# M840X.net
KiCad netlist of a schematic drawn in EAGLE
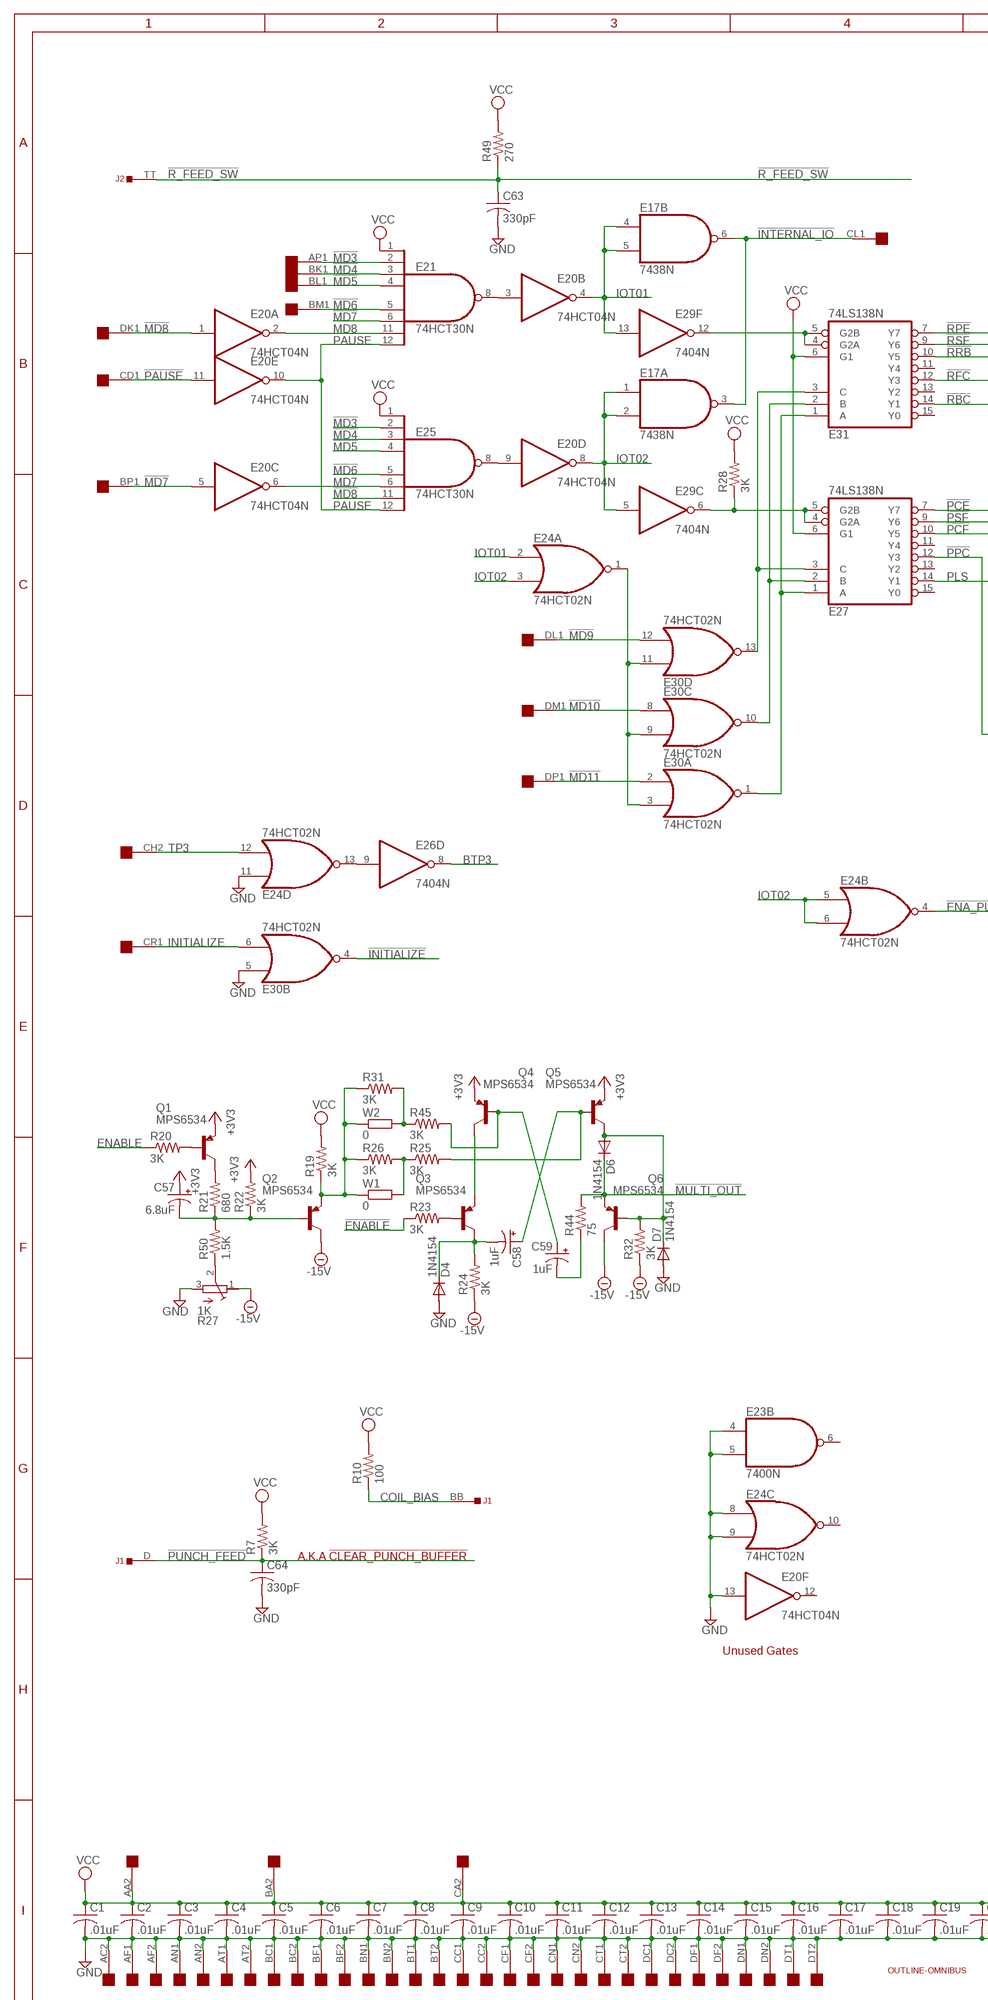
[diagram p0: schematic, sheet 1, part 1 of 2]
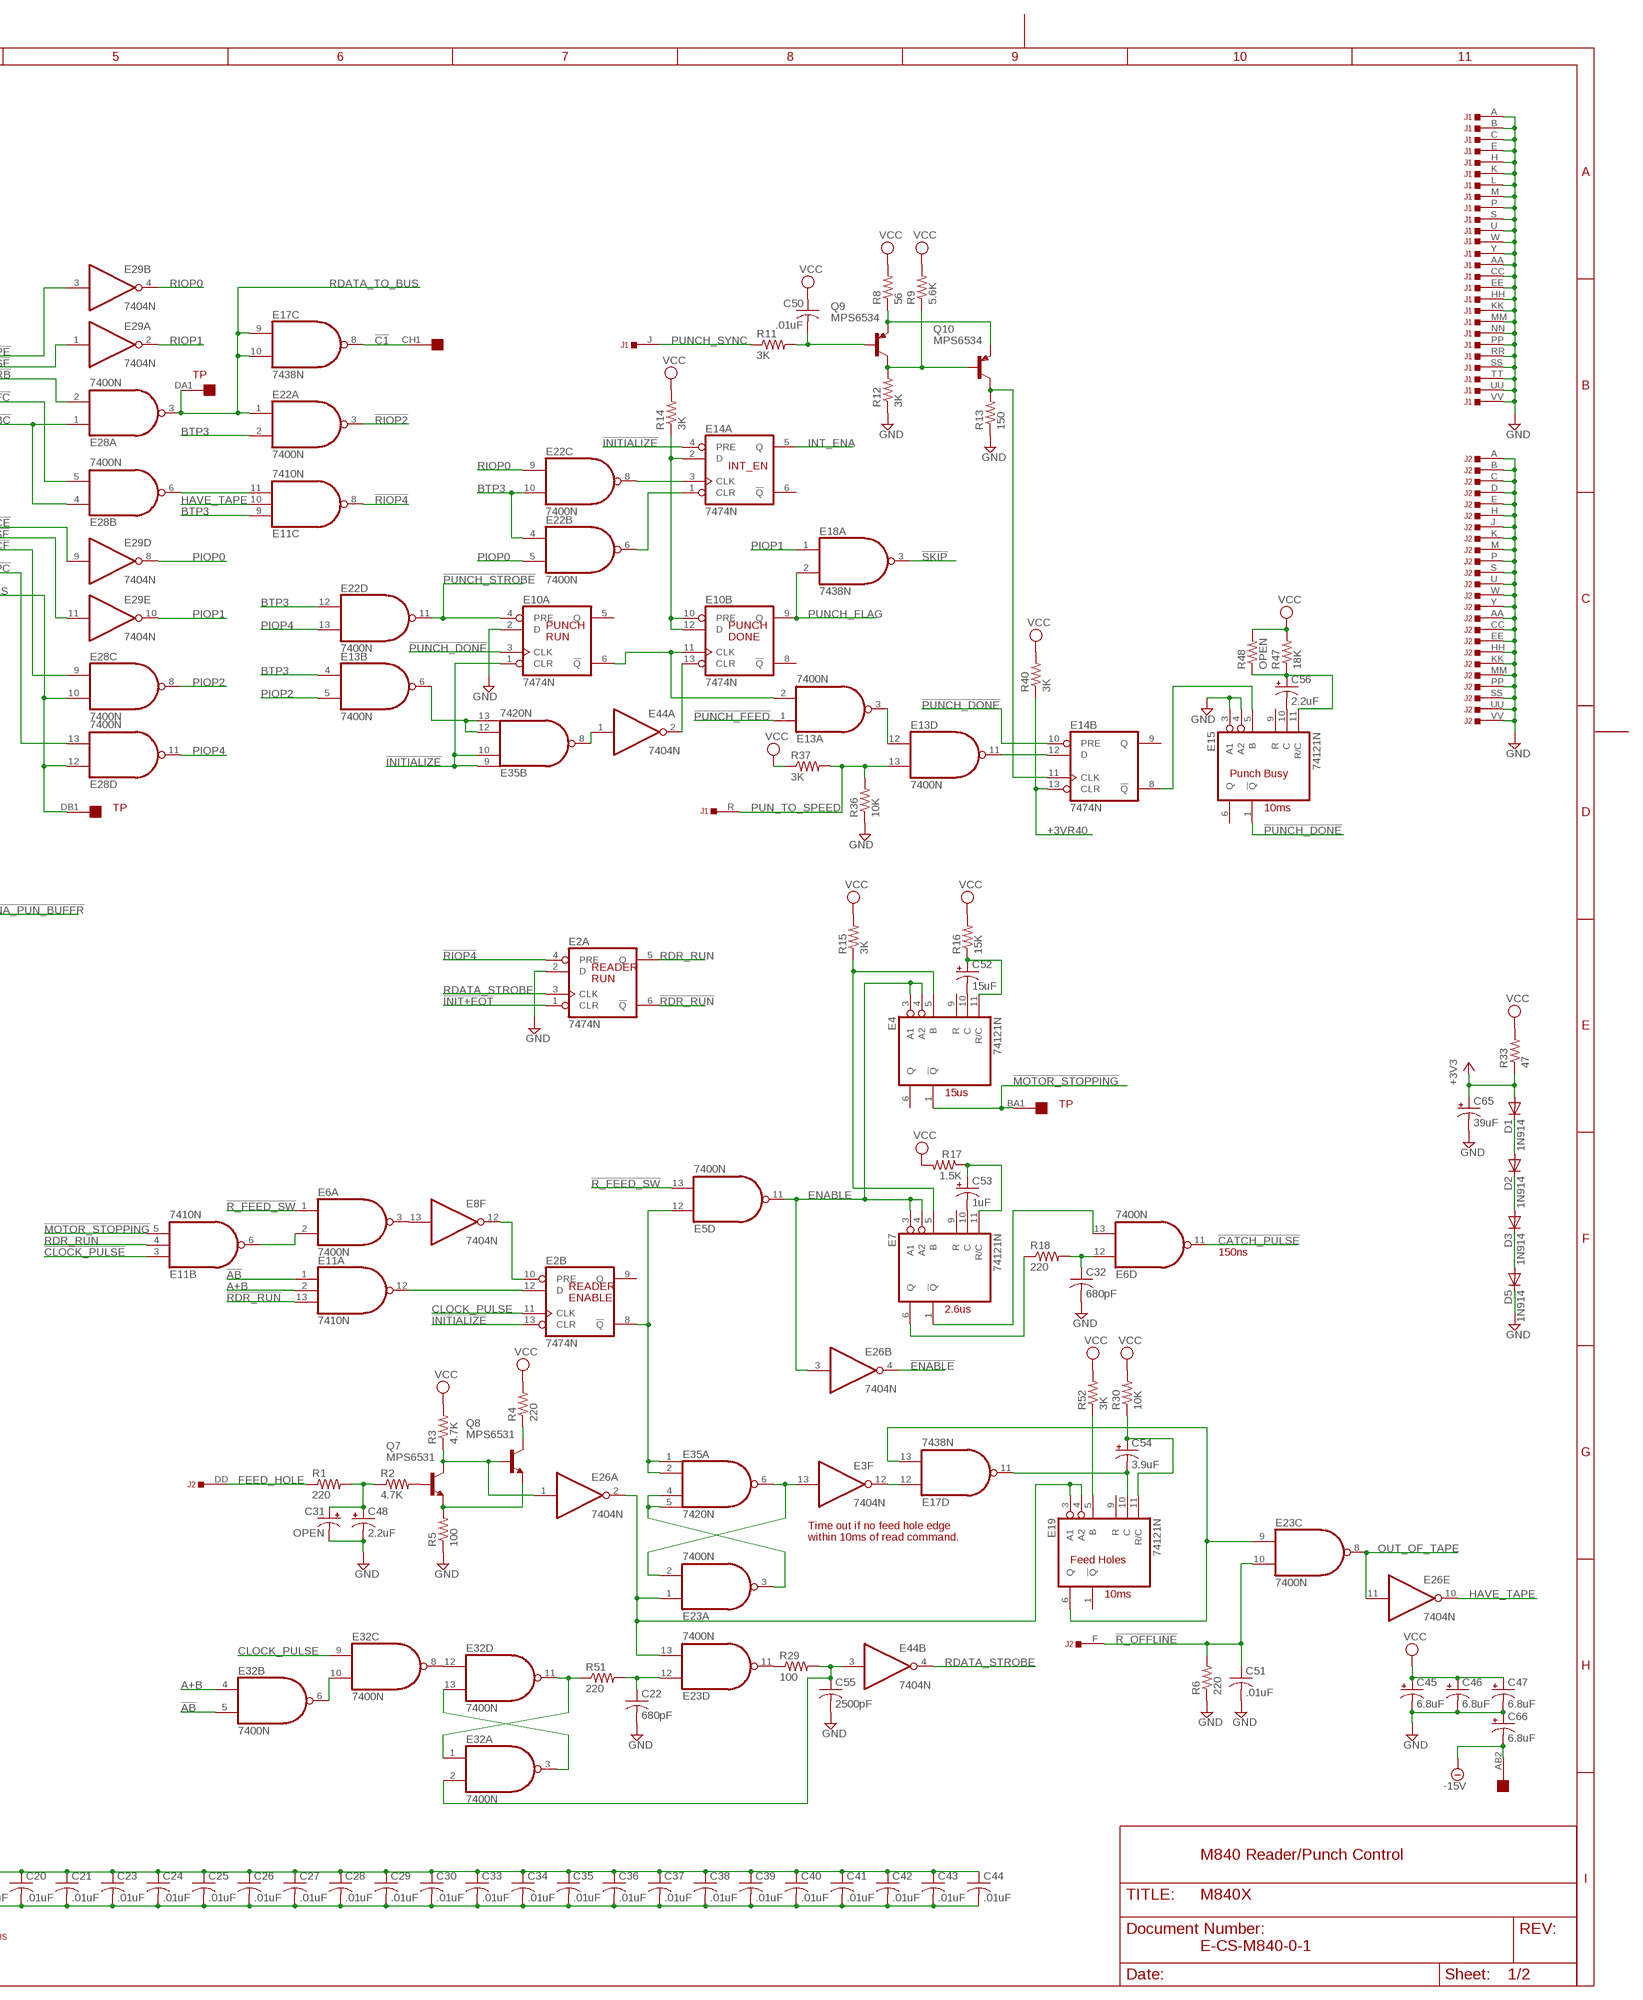
[diagram p1: schematic, sheet 1, part 2 of 2]
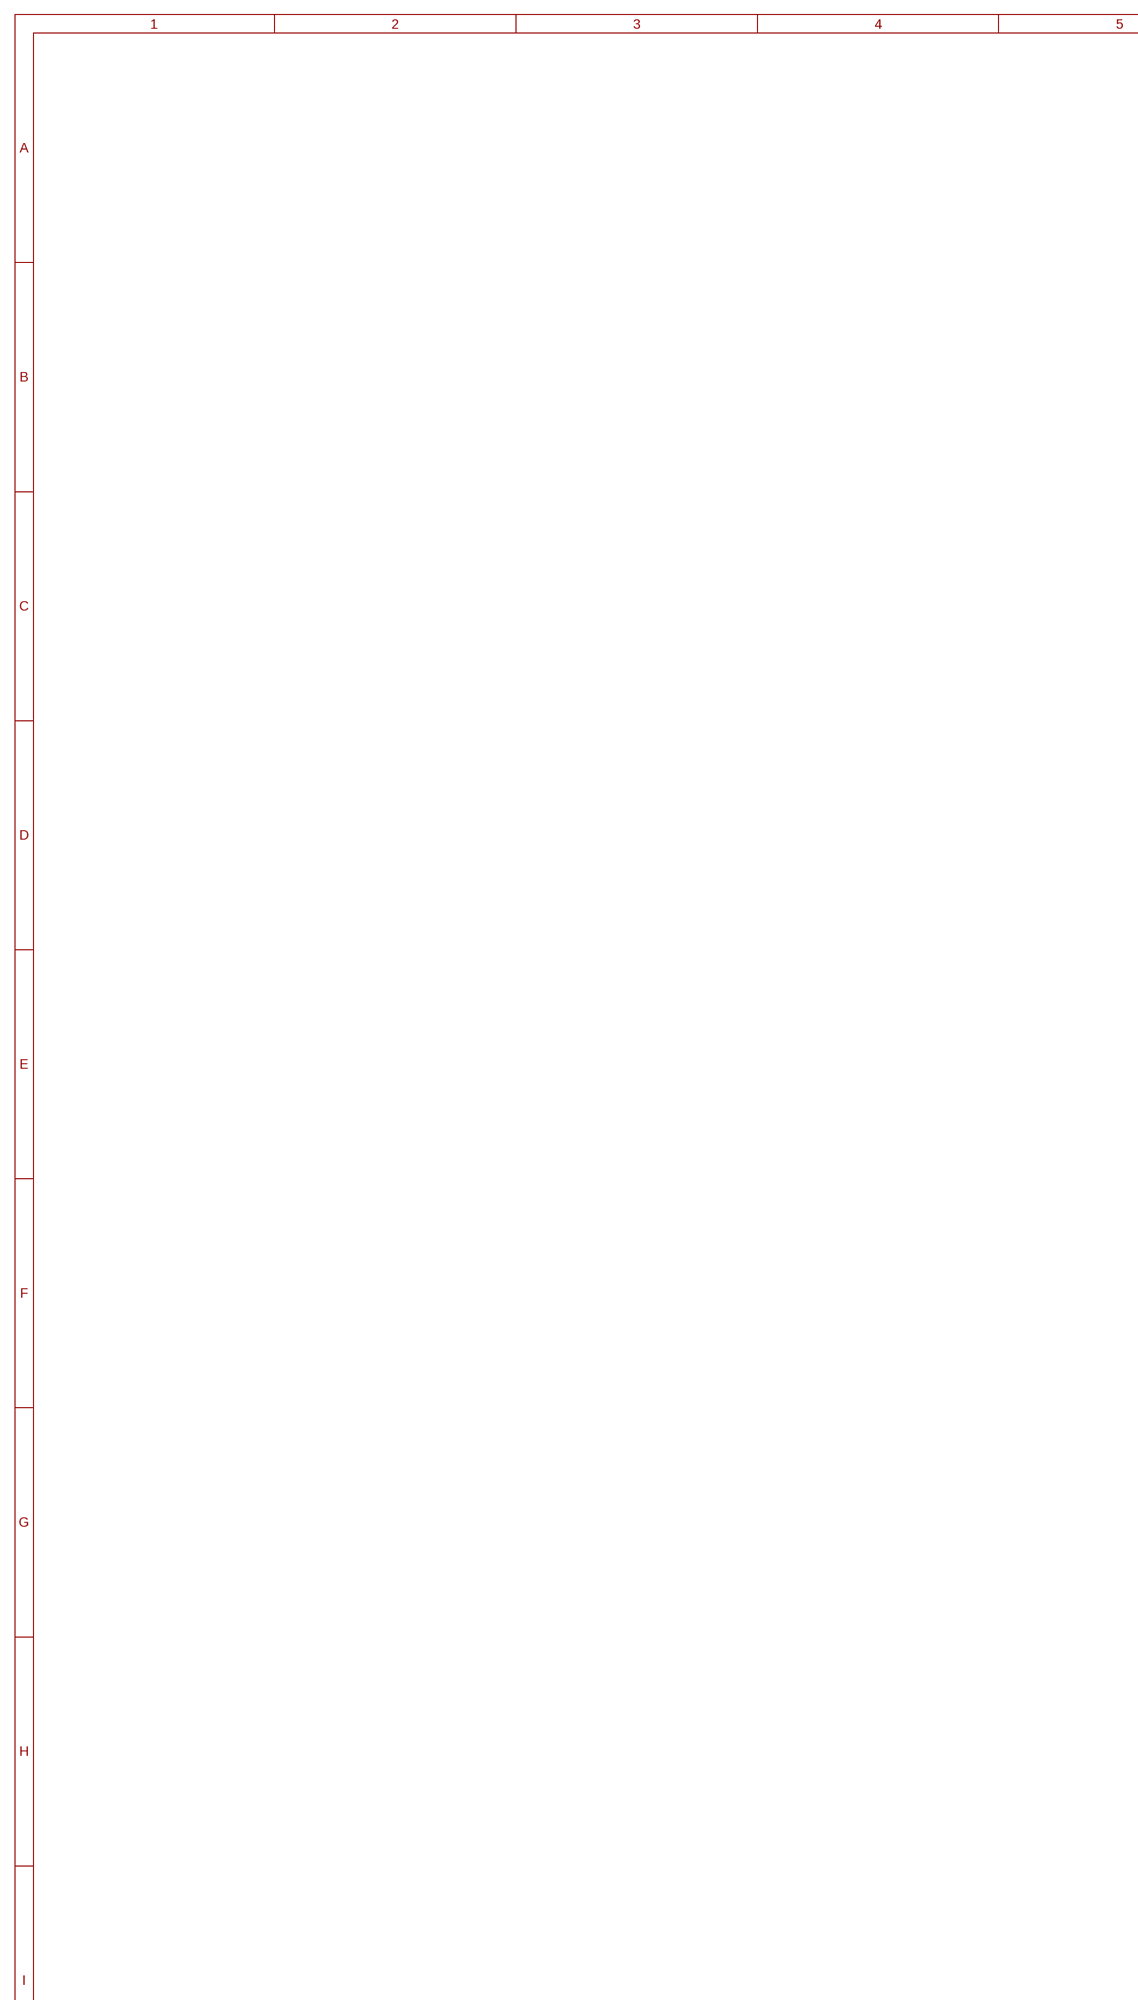
[diagram p2: schematic, sheet 2, part 1 of 2]
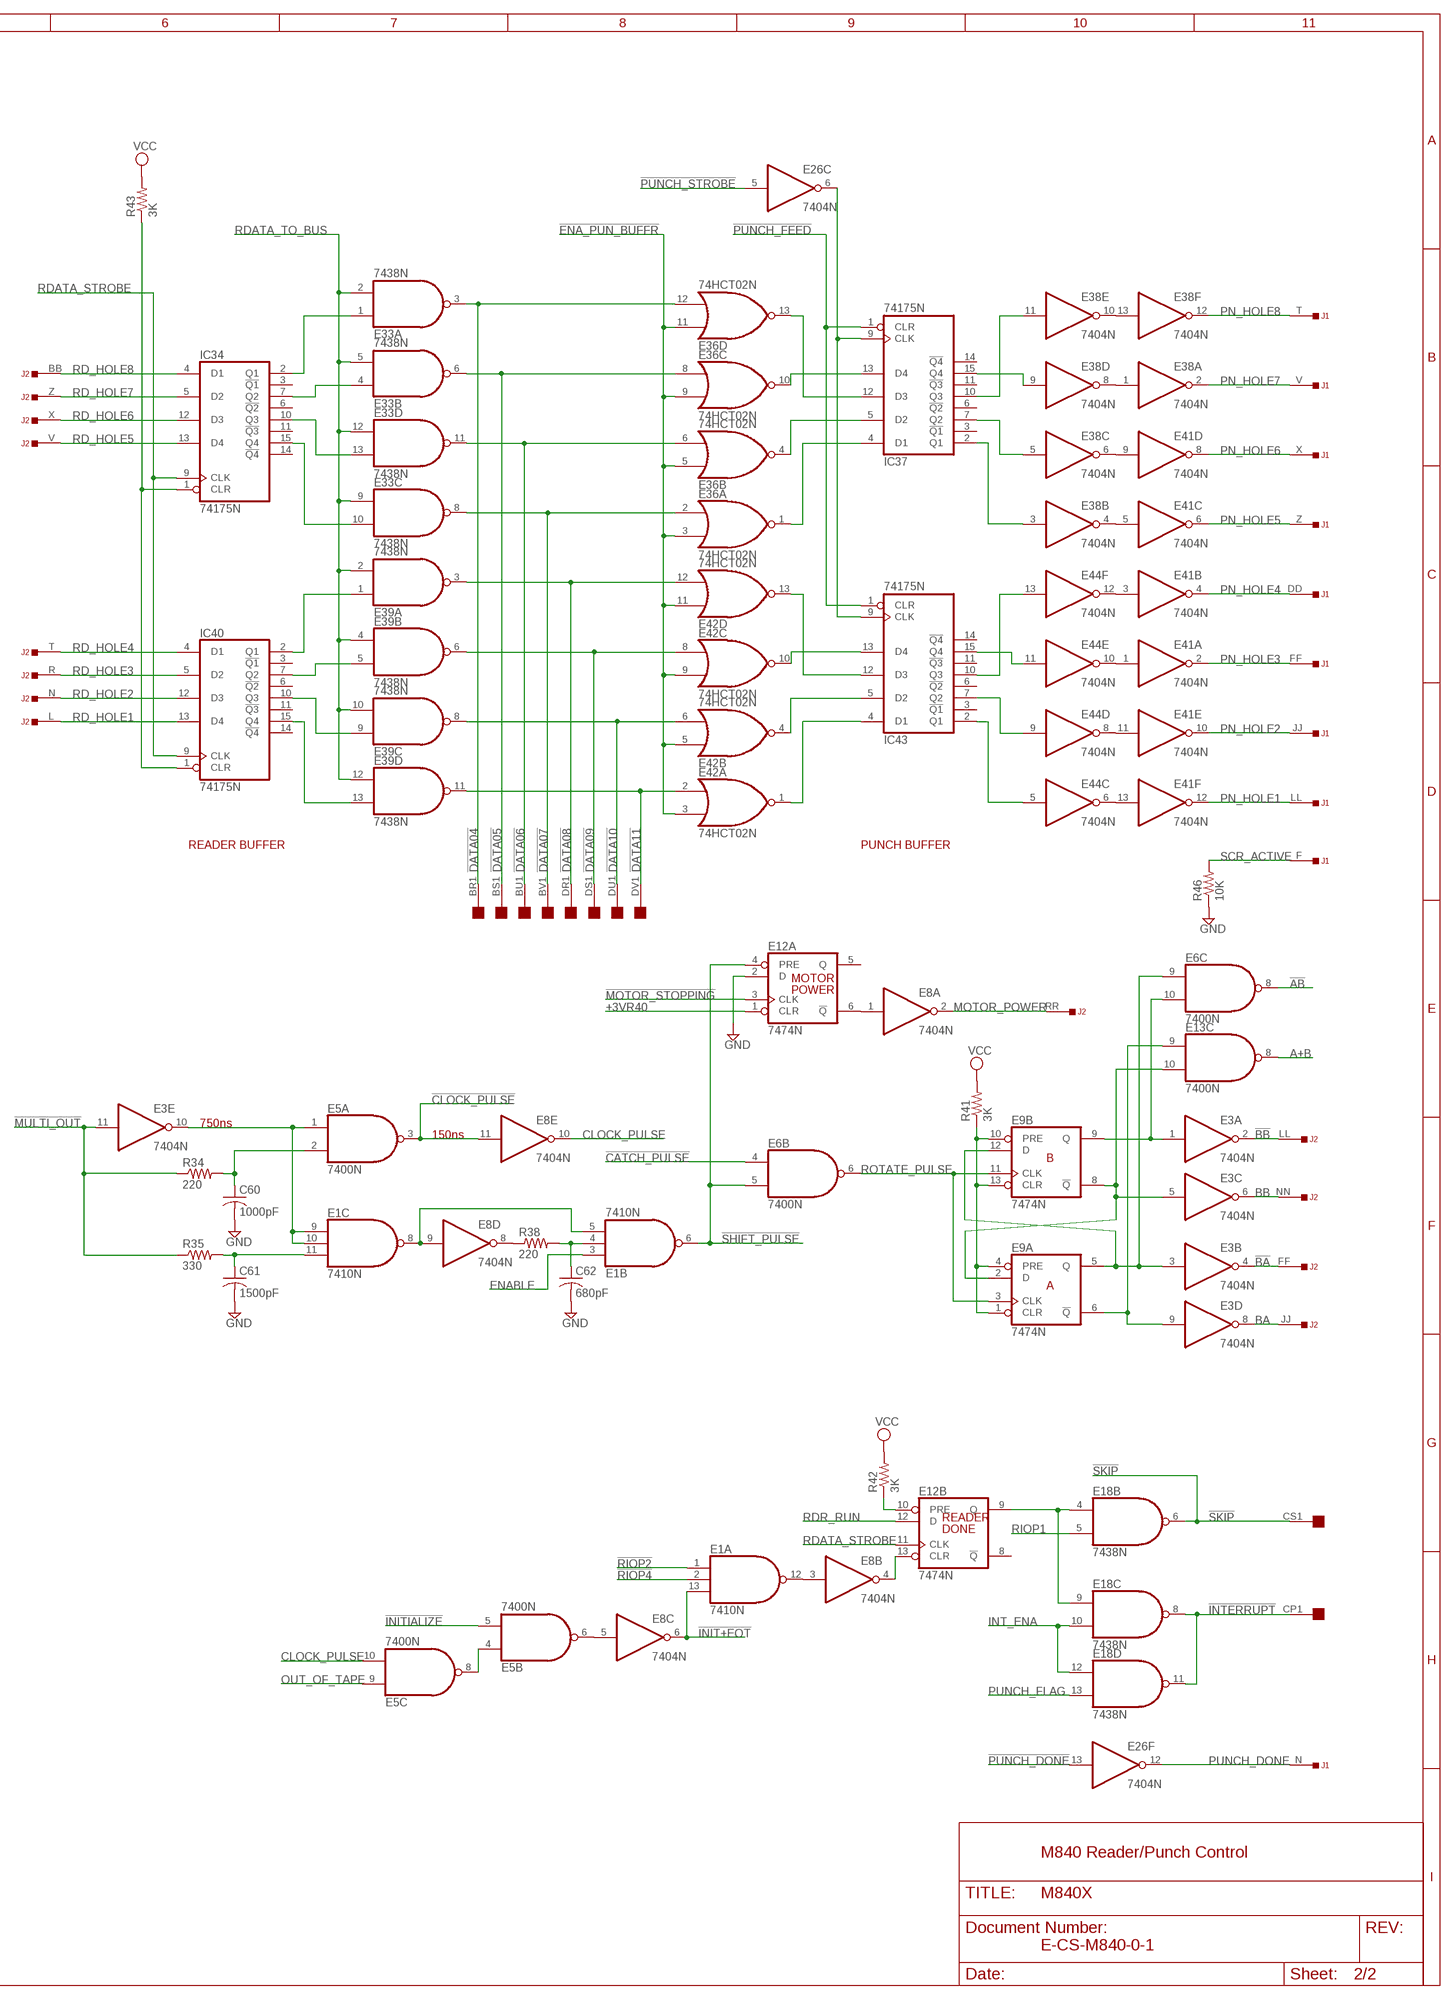
[diagram p3: schematic, sheet 2, part 2 of 2]

(export (version "E")
  (design (tool "Eeschema 10.0.6"))
  (components
    (comp (ref "C1")
      (value ".01uF")
      (footprint "eagle-import:C063-025X075")
      (libsource (lib "eagle-import") (part "C-US"))
    )
    (comp (ref "C2")
      (value ".01uF")
      (footprint "eagle-import:C063-025X075")
      (libsource (lib "eagle-import") (part "C-US"))
    )
    (comp (ref "C3")
      (value ".01uF")
      (footprint "eagle-import:C063-025X075")
      (libsource (lib "eagle-import") (part "C-US"))
    )
    (comp (ref "C4")
      (value ".01uF")
      (footprint "eagle-import:C063-025X075")
      (libsource (lib "eagle-import") (part "C-US"))
    )
    (comp (ref "C5")
      (value ".01uF")
      (footprint "eagle-import:C063-025X075")
      (libsource (lib "eagle-import") (part "C-US"))
    )
    (comp (ref "C6")
      (value ".01uF")
      (footprint "eagle-import:C063-025X075")
      (libsource (lib "eagle-import") (part "C-US"))
    )
    (comp (ref "C7")
      (value ".01uF")
      (footprint "eagle-import:C063-025X075")
      (libsource (lib "eagle-import") (part "C-US"))
    )
    (comp (ref "C8")
      (value ".01uF")
      (footprint "eagle-import:C063-025X075")
      (libsource (lib "eagle-import") (part "C-US"))
    )
    (comp (ref "C9")
      (value ".01uF")
      (footprint "eagle-import:C063-025X075")
      (libsource (lib "eagle-import") (part "C-US"))
    )
    (comp (ref "C10")
      (value ".01uF")
      (footprint "eagle-import:C063-025X075")
      (libsource (lib "eagle-import") (part "C-US"))
    )
    (comp (ref "C11")
      (value ".01uF")
      (footprint "eagle-import:C063-025X075")
      (libsource (lib "eagle-import") (part "C-US"))
    )
    (comp (ref "C12")
      (value ".01uF")
      (footprint "eagle-import:C063-025X075")
      (libsource (lib "eagle-import") (part "C-US"))
    )
    (comp (ref "C13")
      (value ".01uF")
      (footprint "eagle-import:C063-025X075")
      (libsource (lib "eagle-import") (part "C-US"))
    )
    (comp (ref "C14")
      (value ".01uF")
      (footprint "eagle-import:C063-025X075")
      (libsource (lib "eagle-import") (part "C-US"))
    )
    (comp (ref "C15")
      (value ".01uF")
      (footprint "eagle-import:C063-025X075")
      (libsource (lib "eagle-import") (part "C-US"))
    )
    (comp (ref "C16")
      (value ".01uF")
      (footprint "eagle-import:C063-025X075")
      (libsource (lib "eagle-import") (part "C-US"))
    )
    (comp (ref "C17")
      (value ".01uF")
      (footprint "eagle-import:C063-025X075")
      (libsource (lib "eagle-import") (part "C-US"))
    )
    (comp (ref "C18")
      (value ".01uF")
      (footprint "eagle-import:C063-025X075")
      (libsource (lib "eagle-import") (part "C-US"))
    )
    (comp (ref "C19")
      (value ".01uF")
      (footprint "eagle-import:C063-025X075")
      (libsource (lib "eagle-import") (part "C-US"))
    )
    (comp (ref "C20")
      (value ".01uF")
      (footprint "eagle-import:C063-025X075")
      (libsource (lib "eagle-import") (part "C-US"))
    )
    (comp (ref "C21")
      (value ".01uF")
      (footprint "eagle-import:C063-025X075")
      (libsource (lib "eagle-import") (part "C-US"))
    )
    (comp (ref "C22")
      (value "680pF")
      (footprint "eagle-import:C063-025X075")
      (libsource (lib "eagle-import") (part "C-US"))
    )
    (comp (ref "C23")
      (value ".01uF")
      (footprint "eagle-import:C063-025X075")
      (libsource (lib "eagle-import") (part "C-US"))
    )
    (comp (ref "C24")
      (value ".01uF")
      (footprint "eagle-import:C063-025X075")
      (libsource (lib "eagle-import") (part "C-US"))
    )
    (comp (ref "C25")
      (value ".01uF")
      (footprint "eagle-import:C063-025X075")
      (libsource (lib "eagle-import") (part "C-US"))
    )
    (comp (ref "C26")
      (value ".01uF")
      (footprint "eagle-import:C063-025X075")
      (libsource (lib "eagle-import") (part "C-US"))
    )
    (comp (ref "C27")
      (value ".01uF")
      (footprint "eagle-import:C063-025X075")
      (libsource (lib "eagle-import") (part "C-US"))
    )
    (comp (ref "C28")
      (value ".01uF")
      (footprint "eagle-import:C063-025X075")
      (libsource (lib "eagle-import") (part "C-US"))
    )
    (comp (ref "C29")
      (value ".01uF")
      (footprint "eagle-import:C063-025X075")
      (libsource (lib "eagle-import") (part "C-US"))
    )
    (comp (ref "C30")
      (value ".01uF")
      (footprint "eagle-import:C063-025X075")
      (libsource (lib "eagle-import") (part "C-US"))
    )
    (comp (ref "C31")
      (value "OPEN")
      (footprint "eagle-import:E15-5")
      (libsource (lib "eagle-import") (part "CPOL-USE15-5AXIAL"))
    )
    (comp (ref "C32")
      (value "680pF")
      (footprint "eagle-import:C063-025X075")
      (libsource (lib "eagle-import") (part "C-US"))
    )
    (comp (ref "C33")
      (value ".01uF")
      (footprint "eagle-import:C063-025X075")
      (libsource (lib "eagle-import") (part "C-US"))
    )
    (comp (ref "C34")
      (value ".01uF")
      (footprint "eagle-import:C063-025X075")
      (libsource (lib "eagle-import") (part "C-US"))
    )
    (comp (ref "C35")
      (value ".01uF")
      (footprint "eagle-import:C063-025X075")
      (libsource (lib "eagle-import") (part "C-US"))
    )
    (comp (ref "C36")
      (value ".01uF")
      (footprint "eagle-import:C063-025X075")
      (libsource (lib "eagle-import") (part "C-US"))
    )
    (comp (ref "C37")
      (value ".01uF")
      (footprint "eagle-import:C063-025X075")
      (libsource (lib "eagle-import") (part "C-US"))
    )
    (comp (ref "C38")
      (value ".01uF")
      (footprint "eagle-import:C063-025X075")
      (libsource (lib "eagle-import") (part "C-US"))
    )
    (comp (ref "C39")
      (value ".01uF")
      (footprint "eagle-import:C063-025X075")
      (libsource (lib "eagle-import") (part "C-US"))
    )
    (comp (ref "C40")
      (value ".01uF")
      (footprint "eagle-import:C063-025X075")
      (libsource (lib "eagle-import") (part "C-US"))
    )
    (comp (ref "C41")
      (value ".01uF")
      (footprint "eagle-import:C063-025X075")
      (libsource (lib "eagle-import") (part "C-US"))
    )
    (comp (ref "C42")
      (value ".01uF")
      (footprint "eagle-import:C063-025X075")
      (libsource (lib "eagle-import") (part "C-US"))
    )
    (comp (ref "C43")
      (value ".01uF")
      (footprint "eagle-import:C063-025X075")
      (libsource (lib "eagle-import") (part "C-US"))
    )
    (comp (ref "C44")
      (value ".01uF")
      (footprint "eagle-import:C063-025X075")
      (libsource (lib "eagle-import") (part "C-US"))
    )
    (comp (ref "C45")
      (value "6.8uF")
      (footprint "eagle-import:E12-8")
      (libsource (lib "eagle-import") (part "CPOL-USE20-8AXIAL"))
    )
    (comp (ref "C46")
      (value "6.8uF")
      (footprint "eagle-import:E12-8")
      (libsource (lib "eagle-import") (part "CPOL-USE20-8AXIAL"))
    )
    (comp (ref "C47")
      (value "6.8uF")
      (footprint "eagle-import:E12-8")
      (libsource (lib "eagle-import") (part "CPOL-USE20-8AXIAL"))
    )
    (comp (ref "C48")
      (value "2.2uF")
      (footprint "eagle-import:E15-5")
      (libsource (lib "eagle-import") (part "CPOL-USE15-5AXIAL"))
    )
    (comp (ref "C50")
      (value ".01uF")
      (footprint "eagle-import:C203-054-229")
      (libsource (lib "eagle-import") (part "C-US8"))
    )
    (comp (ref "C51")
      (value ".01uF")
      (footprint "eagle-import:C203-054-229")
      (libsource (lib "eagle-import") (part "C-US8"))
    )
    (comp (ref "C52")
      (value "15uF")
      (footprint "eagle-import:E12-8")
      (libsource (lib "eagle-import") (part "CPOL-USE20-8AXIAL"))
    )
    (comp (ref "C53")
      (value "1uF")
      (footprint "eagle-import:E15-5")
      (libsource (lib "eagle-import") (part "CPOL-USE15-5AXIAL"))
    )
    (comp (ref "C54")
      (value "3.9uF")
      (footprint "eagle-import:E15-5")
      (libsource (lib "eagle-import") (part "CPOL-USE15-5AXIAL"))
    )
    (comp (ref "C55")
      (value "2500pF")
      (footprint "eagle-import:C063-025X075")
      (libsource (lib "eagle-import") (part "C-US"))
    )
    (comp (ref "C56")
      (value "2.2uF")
      (footprint "eagle-import:E15-5")
      (libsource (lib "eagle-import") (part "CPOL-USE15-5AXIAL"))
    )
    (comp (ref "C57")
      (value "6.8uF")
      (footprint "eagle-import:E12-8")
      (libsource (lib "eagle-import") (part "CPOL-USE20-8AXIAL"))
    )
    (comp (ref "C58")
      (value "1uF")
      (footprint "eagle-import:E15-5")
      (libsource (lib "eagle-import") (part "CPOL-USE15-5AXIAL"))
    )
    (comp (ref "C59")
      (value "1uF")
      (footprint "eagle-import:E15-5")
      (libsource (lib "eagle-import") (part "CPOL-USE15-5AXIAL"))
    )
    (comp (ref "C63")
      (value "330pF")
      (footprint "eagle-import:C063-025X075")
      (libsource (lib "eagle-import") (part "C-US"))
    )
    (comp (ref "C64")
      (value "330pF")
      (footprint "eagle-import:C063-025X075")
      (libsource (lib "eagle-import") (part "C-US"))
    )
    (comp (ref "C65")
      (value "39uF")
      (footprint "eagle-import:E12-8")
      (libsource (lib "eagle-import") (part "CPOL-USE20-8AXIAL"))
    )
    (comp (ref "C66")
      (value "6.8uF")
      (footprint "eagle-import:E12-8")
      (libsource (lib "eagle-import") (part "CPOL-USE20-8AXIAL"))
    )
    (comp (ref "D1")
      (value "1N914")
      (footprint "eagle-import:DO35-10")
      (libsource (lib "eagle-import") (part "DIODE-DO35-10"))
    )
    (comp (ref "D2")
      (value "1N914")
      (footprint "eagle-import:DO35-10")
      (libsource (lib "eagle-import") (part "DIODE-DO35-10"))
    )
    (comp (ref "D3")
      (value "1N914")
      (footprint "eagle-import:DO35-10")
      (libsource (lib "eagle-import") (part "DIODE-DO35-10"))
    )
    (comp (ref "D4")
      (value "1N4154")
      (footprint "eagle-import:DO35-10")
      (libsource (lib "eagle-import") (part "DIODE-DO35-10"))
    )
    (comp (ref "D5")
      (value "1N914")
      (footprint "eagle-import:DO35-10")
      (libsource (lib "eagle-import") (part "DIODE-DO35-10"))
    )
    (comp (ref "D6")
      (value "1N4154")
      (footprint "eagle-import:DO35-10")
      (libsource (lib "eagle-import") (part "DIODE-DO35-10"))
    )
    (comp (ref "D7")
      (value "1N4154")
      (footprint "eagle-import:DO35-10")
      (libsource (lib "eagle-import") (part "DIODE-DO35-10"))
    )
    (comp (ref "E2")
      (value "7474N")
      (footprint "eagle-import:DIL14")
      (libsource (lib "eagle-import") (part "7474NS"))
    )
    (comp (ref "E3")
      (value "7404N")
      (footprint "eagle-import:DIL14")
      (libsource (lib "eagle-import") (part "7404N"))
    )
    (comp (ref "E4")
      (value "74121N")
      (footprint "eagle-import:DIL14")
      (libsource (lib "eagle-import") (part "74121N"))
    )
    (comp (ref "E5")
      (value "7400N")
      (footprint "eagle-import:DIL14")
      (libsource (lib "eagle-import") (part "7400N"))
    )
    (comp (ref "E6")
      (value "7400N")
      (footprint "eagle-import:DIL14")
      (libsource (lib "eagle-import") (part "7400N"))
    )
    (comp (ref "E7")
      (value "74121N")
      (footprint "eagle-import:DIL14")
      (libsource (lib "eagle-import") (part "74121N"))
    )
    (comp (ref "E8")
      (value "7404N")
      (footprint "eagle-import:DIL14")
      (libsource (lib "eagle-import") (part "7404N"))
    )
    (comp (ref "E10")
      (value "7474N")
      (footprint "eagle-import:DIL14")
      (libsource (lib "eagle-import") (part "7474NS"))
    )
    (comp (ref "E11")
      (value "7410N")
      (footprint "eagle-import:DIL14")
      (libsource (lib "eagle-import") (part "7410N"))
    )
    (comp (ref "E13")
      (value "7400N")
      (footprint "eagle-import:DIL14")
      (libsource (lib "eagle-import") (part "7400N"))
    )
    (comp (ref "E14")
      (value "7474N")
      (footprint "eagle-import:DIL14")
      (libsource (lib "eagle-import") (part "7474NS"))
    )
    (comp (ref "E15")
      (value "74121N")
      (footprint "eagle-import:DIL14")
      (libsource (lib "eagle-import") (part "74121N"))
    )
    (comp (ref "E17")
      (value "7438N")
      (footprint "eagle-import:DIL14")
      (libsource (lib "eagle-import") (part "7438N"))
    )
    (comp (ref "E18")
      (value "7438N")
      (footprint "eagle-import:DIL14")
      (libsource (lib "eagle-import") (part "7438N"))
    )
    (comp (ref "E19")
      (value "74121N")
      (footprint "eagle-import:DIL14")
      (libsource (lib "eagle-import") (part "74121N"))
    )
    (comp (ref "E20")
      (value "74HCT04N")
      (footprint "eagle-import:DIL14")
      (libsource (lib "eagle-import") (part "7404N"))
    )
    (comp (ref "E21")
      (value "74HCT30N")
      (footprint "eagle-import:DIL14")
      (libsource (lib "eagle-import") (part "7430NLS"))
    )
    (comp (ref "E22")
      (value "7400N")
      (footprint "eagle-import:DIL14")
      (libsource (lib "eagle-import") (part "7400N"))
    )
    (comp (ref "E23")
      (value "7400N")
      (footprint "eagle-import:DIL14")
      (libsource (lib "eagle-import") (part "7400N"))
    )
    (comp (ref "E24")
      (value "74HCT02N")
      (footprint "eagle-import:DIL14")
      (libsource (lib "eagle-import") (part "7402NLS"))
    )
    (comp (ref "E25")
      (value "74HCT30N")
      (footprint "eagle-import:DIL14")
      (libsource (lib "eagle-import") (part "7430NLS"))
    )
    (comp (ref "E26")
      (value "7404N")
      (footprint "eagle-import:DIL14")
      (libsource (lib "eagle-import") (part "7404N"))
    )
    (comp (ref "E27")
      (value "74LS138N")
      (footprint "eagle-import:DIL16")
      (libsource (lib "eagle-import") (part "74138NS"))
    )
    (comp (ref "E28")
      (value "7400N")
      (footprint "eagle-import:DIL14")
      (libsource (lib "eagle-import") (part "7400N"))
    )
    (comp (ref "E29")
      (value "7404N")
      (footprint "eagle-import:DIL14")
      (libsource (lib "eagle-import") (part "7404N"))
    )
    (comp (ref "E30")
      (value "74HCT02N")
      (footprint "eagle-import:DIL14")
      (libsource (lib "eagle-import") (part "7402NLS"))
    )
    (comp (ref "E31")
      (value "74LS138N")
      (footprint "eagle-import:DIL16")
      (libsource (lib "eagle-import") (part "74138NS"))
    )
    (comp (ref "E32")
      (value "7400N")
      (footprint "eagle-import:DIL14")
      (libsource (lib "eagle-import") (part "7400N"))
    )
    (comp (ref "E35")
      (value "7420N")
      (footprint "eagle-import:DIL14")
      (libsource (lib "eagle-import") (part "7420N"))
    )
    (comp (ref "E44")
      (value "7404N")
      (footprint "eagle-import:DIL14")
      (libsource (lib "eagle-import") (part "7404N"))
    )
    (comp (ref "J1")
      (value "DEC40PINSH")
      (footprint "eagle-import:DEC40PINH")
      (libsource (lib "eagle-import") (part "DEC40PINSH"))
    )
    (comp (ref "J2")
      (value "DEC40PINSH")
      (footprint "eagle-import:DEC40PINH")
      (libsource (lib "eagle-import") (part "DEC40PINSH"))
    )
    (comp (ref "OMNIBUS")
      (value "QUAD")
      (footprint "eagle-import:EDGE-CON8")
      (libsource (lib "eagle-import") (part "QUAD"))
    )
    (comp (ref "Q1")
      (value "MPS6534")
      (footprint "eagle-import:TO5")
      (libsource (lib "eagle-import") (part "-PNP-TO5"))
    )
    (comp (ref "Q2")
      (value "MPS6534")
      (footprint "eagle-import:TO5")
      (libsource (lib "eagle-import") (part "-PNP-TO5"))
    )
    (comp (ref "Q3")
      (value "MPS6534")
      (footprint "eagle-import:TO5")
      (libsource (lib "eagle-import") (part "-PNP-TO5"))
    )
    (comp (ref "Q4")
      (value "MPS6534")
      (footprint "eagle-import:TO5")
      (libsource (lib "eagle-import") (part "-PNP-TO5"))
    )
    (comp (ref "Q5")
      (value "MPS6534")
      (footprint "eagle-import:TO5")
      (libsource (lib "eagle-import") (part "-PNP-TO5"))
    )
    (comp (ref "Q6")
      (value "MPS6534")
      (footprint "eagle-import:TO5")
      (libsource (lib "eagle-import") (part "-PNP-TO5"))
    )
    (comp (ref "Q7")
      (value "MPS6531")
      (footprint "eagle-import:TO5")
      (libsource (lib "eagle-import") (part "-NPN-TO5"))
    )
    (comp (ref "Q8")
      (value "MPS6531")
      (footprint "eagle-import:TO5")
      (libsource (lib "eagle-import") (part "-NPN-TO5"))
    )
    (comp (ref "Q9")
      (value "MPS6534")
      (footprint "eagle-import:TO5")
      (libsource (lib "eagle-import") (part "-PNP-TO5"))
    )
    (comp (ref "Q10")
      (value "MPS6534")
      (footprint "eagle-import:TO5")
      (libsource (lib "eagle-import") (part "-PNP-TO5"))
    )
    (comp (ref "R1")
      (value "220")
      (footprint "eagle-import:0207_10")
      (libsource (lib "eagle-import") (part "R-US_0207/10"))
    )
    (comp (ref "R2")
      (value "4.7K")
      (footprint "eagle-import:0207_10")
      (libsource (lib "eagle-import") (part "R-US_0207/10"))
    )
    (comp (ref "R3")
      (value "4.7K")
      (footprint "eagle-import:0207_10")
      (libsource (lib "eagle-import") (part "R-US_0207/10"))
    )
    (comp (ref "R4")
      (value "220")
      (footprint "eagle-import:0207_10")
      (libsource (lib "eagle-import") (part "R-US_0207/10"))
    )
    (comp (ref "R5")
      (value "100")
      (footprint "eagle-import:0207_10")
      (libsource (lib "eagle-import") (part "R-US_0207/10"))
    )
    (comp (ref "R6")
      (value "220")
      (footprint "eagle-import:0207_10")
      (libsource (lib "eagle-import") (part "R-US_0207/10"))
    )
    (comp (ref "R7")
      (value "3K")
      (footprint "eagle-import:0207_10")
      (libsource (lib "eagle-import") (part "R-US_0207/10"))
    )
    (comp (ref "R8")
      (value "56")
      (footprint "eagle-import:0207_10")
      (libsource (lib "eagle-import") (part "R-US_0207/10"))
    )
    (comp (ref "R9")
      (value "5.6K")
      (footprint "eagle-import:0207_10")
      (libsource (lib "eagle-import") (part "R-US_0207/10"))
    )
    (comp (ref "R10")
      (value "100")
      (footprint "eagle-import:0207_10")
      (libsource (lib "eagle-import") (part "R-US_0207/10"))
    )
    (comp (ref "R11")
      (value "3K")
      (footprint "eagle-import:0207_10")
      (libsource (lib "eagle-import") (part "R-US_0207/10"))
    )
    (comp (ref "R12")
      (value "3K")
      (footprint "eagle-import:0207_10")
      (libsource (lib "eagle-import") (part "R-US_0207/10"))
    )
    (comp (ref "R13")
      (value "150")
      (footprint "eagle-import:0207_10")
      (libsource (lib "eagle-import") (part "R-US_0207/10"))
    )
    (comp (ref "R14")
      (value "3K")
      (footprint "eagle-import:0207_10")
      (libsource (lib "eagle-import") (part "R-US_0207/10"))
    )
    (comp (ref "R15")
      (value "3K")
      (footprint "eagle-import:0207_10")
      (libsource (lib "eagle-import") (part "R-US_0207/10"))
    )
    (comp (ref "R16")
      (value "15K")
      (footprint "eagle-import:0207_10")
      (libsource (lib "eagle-import") (part "R-US_0207/10"))
    )
    (comp (ref "R17")
      (value "1.5K")
      (footprint "eagle-import:0207_10")
      (libsource (lib "eagle-import") (part "R-US_0207/10"))
    )
    (comp (ref "R18")
      (value "220")
      (footprint "eagle-import:0207_10")
      (libsource (lib "eagle-import") (part "R-US_0207/10"))
    )
    (comp (ref "R19")
      (value "3K")
      (footprint "eagle-import:0207_10")
      (libsource (lib "eagle-import") (part "R-US_0207/10"))
    )
    (comp (ref "R20")
      (value "3K")
      (footprint "eagle-import:0207_10")
      (libsource (lib "eagle-import") (part "R-US_0207/10"))
    )
    (comp (ref "R21")
      (value "680")
      (footprint "eagle-import:0207_10")
      (libsource (lib "eagle-import") (part "R-US_0207/10"))
    )
    (comp (ref "R22")
      (value "3K")
      (footprint "eagle-import:0207_10")
      (libsource (lib "eagle-import") (part "R-US_0207/10"))
    )
    (comp (ref "R23")
      (value "3K")
      (footprint "eagle-import:0207_10")
      (libsource (lib "eagle-import") (part "R-US_0207/10"))
    )
    (comp (ref "R24")
      (value "3K")
      (footprint "eagle-import:0207_10")
      (libsource (lib "eagle-import") (part "R-US_0207/10"))
    )
    (comp (ref "R25")
      (value "3K")
      (footprint "eagle-import:0207_10")
      (libsource (lib "eagle-import") (part "R-US_0207/10"))
    )
    (comp (ref "R26")
      (value "3K")
      (footprint "eagle-import:0207_10")
      (libsource (lib "eagle-import") (part "R-US_0207/10"))
    )
    (comp (ref "R27")
      (value "1K")
      (footprint "eagle-import:3006Y")
      (libsource (lib "eagle-import") (part "275P"))
    )
    (comp (ref "R28")
      (value "3K")
      (footprint "eagle-import:0207_10")
      (libsource (lib "eagle-import") (part "R-US_0207/10"))
    )
    (comp (ref "R29")
      (value "100")
      (footprint "eagle-import:0207_10")
      (libsource (lib "eagle-import") (part "R-US_0207/10"))
    )
    (comp (ref "R30")
      (value "10K")
      (footprint "eagle-import:0207_10")
      (libsource (lib "eagle-import") (part "R-US_0207/10"))
    )
    (comp (ref "R31")
      (value "3K")
      (footprint "eagle-import:0207_10")
      (libsource (lib "eagle-import") (part "R-US_0207/10"))
    )
    (comp (ref "R32")
      (value "3K")
      (footprint "eagle-import:0207_10")
      (libsource (lib "eagle-import") (part "R-US_0207/10"))
    )
    (comp (ref "R33")
      (value "47")
      (footprint "eagle-import:0207_10")
      (libsource (lib "eagle-import") (part "R-US_0207/10"))
    )
    (comp (ref "R36")
      (value "10K")
      (footprint "eagle-import:0207_10")
      (libsource (lib "eagle-import") (part "R-US_0207/10"))
    )
    (comp (ref "R37")
      (value "3K")
      (footprint "eagle-import:0207_10")
      (libsource (lib "eagle-import") (part "R-US_0207/10"))
    )
    (comp (ref "R40")
      (value "3K")
      (footprint "eagle-import:0207_10")
      (libsource (lib "eagle-import") (part "R-US_0207/10"))
    )
    (comp (ref "R44")
      (value "75")
      (footprint "eagle-import:0207_10")
      (libsource (lib "eagle-import") (part "R-US_0207/10"))
    )
    (comp (ref "R45")
      (value "3K")
      (footprint "eagle-import:0207_10")
      (libsource (lib "eagle-import") (part "R-US_0207/10"))
    )
    (comp (ref "R47")
      (value "18K")
      (footprint "eagle-import:0207_10")
      (libsource (lib "eagle-import") (part "R-US_0207/10"))
    )
    (comp (ref "R48")
      (value "OPEN")
      (footprint "eagle-import:0207_10")
      (libsource (lib "eagle-import") (part "R-US_0207/10"))
    )
    (comp (ref "R49")
      (value "270")
      (footprint "eagle-import:0207_10")
      (libsource (lib "eagle-import") (part "R-US_0207/10"))
    )
    (comp (ref "R50")
      (value "1.5K")
      (footprint "eagle-import:0207_10")
      (libsource (lib "eagle-import") (part "R-US_0207/10"))
    )
    (comp (ref "R51")
      (value "220")
      (footprint "eagle-import:0207_10")
      (libsource (lib "eagle-import") (part "R-US_0207/10"))
    )
    (comp (ref "R52")
      (value "3K")
      (footprint "eagle-import:0207_10")
      (libsource (lib "eagle-import") (part "R-US_0207/10"))
    )
    (comp (ref "U$1")
      (value "OUTLINE-OMNIBUS")
      (footprint "eagle-import:OMNIBUS")
      (libsource (lib "eagle-import") (part "OUTLINE-OMNIBUS"))
    )
    (comp (ref "W1")
      (value "0")
      (footprint "eagle-import:0207_10")
      (libsource (lib "eagle-import") (part "R-EU_0207/10"))
    )
    (comp (ref "W2")
      (value "0")
      (footprint "eagle-import:0207_10")
      (libsource (lib "eagle-import") (part "R-EU_0207/10"))
    )
    (comp (ref "C60")
      (value "1000pF")
      (footprint "eagle-import:C063-025X075")
      (libsource (lib "eagle-import") (part "C-US"))
    )
    (comp (ref "C61")
      (value "1500pF")
      (footprint "eagle-import:C063-025X075")
      (libsource (lib "eagle-import") (part "C-US"))
    )
    (comp (ref "C62")
      (value "680pF")
      (footprint "eagle-import:C063-025X075")
      (libsource (lib "eagle-import") (part "C-US"))
    )
    (comp (ref "E1")
      (value "7410N")
      (footprint "eagle-import:DIL14")
      (libsource (lib "eagle-import") (part "7410N"))
    )
    (comp (ref "E9")
      (value "7474N")
      (footprint "eagle-import:DIL14")
      (libsource (lib "eagle-import") (part "7474NS"))
    )
    (comp (ref "E12")
      (value "7474N")
      (footprint "eagle-import:DIL14")
      (libsource (lib "eagle-import") (part "7474NS"))
    )
    (comp (ref "E33")
      (value "7438N")
      (footprint "eagle-import:DIL14")
      (libsource (lib "eagle-import") (part "7438N"))
    )
    (comp (ref "E36")
      (value "74HCT02N")
      (footprint "eagle-import:DIL14")
      (libsource (lib "eagle-import") (part "7402NLS"))
    )
    (comp (ref "E38")
      (value "7404N")
      (footprint "eagle-import:DIL14")
      (libsource (lib "eagle-import") (part "7404N"))
    )
    (comp (ref "E39")
      (value "7438N")
      (footprint "eagle-import:DIL14")
      (libsource (lib "eagle-import") (part "7438N"))
    )
    (comp (ref "E41")
      (value "7404N")
      (footprint "eagle-import:DIL14")
      (libsource (lib "eagle-import") (part "7404N"))
    )
    (comp (ref "E42")
      (value "74HCT02N")
      (footprint "eagle-import:DIL14")
      (libsource (lib "eagle-import") (part "7402NLS"))
    )
    (comp (ref "IC34")
      (value "74175N")
      (footprint "eagle-import:DIL16")
      (libsource (lib "eagle-import") (part "74175N"))
    )
    (comp (ref "IC37")
      (value "74175N")
      (footprint "eagle-import:DIL16")
      (libsource (lib "eagle-import") (part "74175N"))
    )
    (comp (ref "IC40")
      (value "74175N")
      (footprint "eagle-import:DIL16")
      (libsource (lib "eagle-import") (part "74175N"))
    )
    (comp (ref "IC43")
      (value "74175N")
      (footprint "eagle-import:DIL16")
      (libsource (lib "eagle-import") (part "74175N"))
    )
    (comp (ref "R34")
      (value "220")
      (footprint "eagle-import:0207_10")
      (libsource (lib "eagle-import") (part "R-US_0207/10"))
    )
    (comp (ref "R35")
      (value "330")
      (footprint "eagle-import:0207_10")
      (libsource (lib "eagle-import") (part "R-US_0207/10"))
    )
    (comp (ref "R38")
      (value "220")
      (footprint "eagle-import:0207_10")
      (libsource (lib "eagle-import") (part "R-US_0207/10"))
    )
    (comp (ref "R41")
      (value "3K")
      (footprint "eagle-import:0207_10")
      (libsource (lib "eagle-import") (part "R-US_0207/10"))
    )
    (comp (ref "R42")
      (value "3K")
      (footprint "eagle-import:0207_10")
      (libsource (lib "eagle-import") (part "R-US_0207/10"))
    )
    (comp (ref "R43")
      (value "3K")
      (footprint "eagle-import:0207_10")
      (libsource (lib "eagle-import") (part "R-US_0207/10"))
    )
    (comp (ref "R46")
      (value "10K")
      (footprint "eagle-import:0207_10")
      (libsource (lib "eagle-import") (part "R-US_0207/10"))
    )
  )
  (nets
    (net (code "1") (name "+3V3") (class "Default")
      (node (ref "C57") (pin "+") (pinfunction "+_+") (pintype "passive"))
      (node (ref "C65") (pin "+") (pinfunction "+_+") (pintype "passive"))
      (node (ref "D1") (pin "A") (pinfunction "A_A") (pintype "passive"))
      (node (ref "Q1") (pin "1") (pinfunction "E_1") (pintype "passive"))
      (node (ref "Q4") (pin "1") (pinfunction "E_1") (pintype "passive"))
      (node (ref "Q5") (pin "1") (pinfunction "E_1") (pintype "passive"))
      (node (ref "R22") (pin "2") (pinfunction "2_2") (pintype "passive"))
      (node (ref "R33") (pin "1") (pinfunction "1_1") (pintype "passive"))
    )
    (net (code "2") (name "+3VR40") (class "Default")
      (node (ref "E12") (pin "1") (pinfunction "CLR_1") (pintype "input"))
      (node (ref "E14") (pin "13") (pinfunction "CLR_13") (pintype "input"))
      (node (ref "R40") (pin "1") (pinfunction "1_1") (pintype "passive"))
    )
    (net (code "3") (name "-15V") (class "Default")
      (node (ref "C66") (pin "-") (pinfunction "-_-") (pintype "passive"))
      (node (ref "OMNIBUS") (pin "AB2") (pinfunction "1_AB2") (pintype "bidirectional"))
      (node (ref "Q2") (pin "3") (pinfunction "C_3") (pintype "passive"))
      (node (ref "Q6") (pin "3") (pinfunction "C_3") (pintype "passive"))
      (node (ref "R24") (pin "1") (pinfunction "1_1") (pintype "passive"))
      (node (ref "R27") (pin "1") (pinfunction "A_1") (pintype "passive"))
      (node (ref "R32") (pin "1") (pinfunction "1_1") (pintype "passive"))
    )
    (net (code "4") (name "A+B") (class "Default")
      (node (ref "E11") (pin "2") (pinfunction "I1_2") (pintype "input"))
      (node (ref "E13") (pin "8") (pinfunction "O_8") (pintype "output"))
      (node (ref "E32") (pin "4") (pinfunction "I0_4") (pintype "input"))
    )
    (net (code "5") (name "BA") (class "Default")
      (node (ref "E3") (pin "8") (pinfunction "O_8") (pintype "output"))
      (node (ref "J2") (pin "JJ") (pinfunction "P_JJ") (pintype "passive"))
    )
    (net (code "6") (name "BB") (class "Default")
      (node (ref "E3") (pin "6") (pinfunction "O_6") (pintype "output"))
      (node (ref "J2") (pin "NN") (pinfunction "P_NN") (pintype "passive"))
    )
    (net (code "7") (name "BTP3") (class "Default")
      (node (ref "E11") (pin "9") (pinfunction "I0_9") (pintype "input"))
      (node (ref "E13") (pin "4") (pinfunction "I0_4") (pintype "input"))
      (node (ref "E22") (pin "10") (pinfunction "I1_10") (pintype "input"))
      (node (ref "E22") (pin "12") (pinfunction "I0_12") (pintype "input"))
      (node (ref "E22") (pin "2") (pinfunction "I1_2") (pintype "input"))
      (node (ref "E22") (pin "4") (pinfunction "I0_4") (pintype "input"))
      (node (ref "E26") (pin "8") (pinfunction "O_8") (pintype "output"))
    )
    (net (code "8") (name "CLOCK_PULSE") (class "Default")
      (node (ref "E2") (pin "11") (pinfunction "CLK_11") (pintype "input"))
      (node (ref "E32") (pin "9") (pinfunction "I0_9") (pintype "input"))
      (node (ref "E5") (pin "10") (pinfunction "I1_10") (pintype "input"))
      (node (ref "E8") (pin "10") (pinfunction "O_10") (pintype "output"))
    )
    (net (code "9") (name "COIL_BIAS") (class "Default")
      (node (ref "J1") (pin "BB") (pinfunction "P_BB") (pintype "passive"))
      (node (ref "R10") (pin "1") (pinfunction "1_1") (pintype "passive"))
    )
    (net (code "10") (name "ENABLE") (class "Default")
      (node (ref "E1") (pin "3") (pinfunction "I0_3") (pintype "input"))
      (node (ref "E26") (pin "3") (pinfunction "I_3") (pintype "input"))
      (node (ref "E4") (pin "3") (pinfunction "A1_3") (pintype "input"))
      (node (ref "E4") (pin "4") (pinfunction "A2_4") (pintype "input"))
      (node (ref "E5") (pin "11") (pinfunction "O_11") (pintype "output"))
      (node (ref "E7") (pin "3") (pinfunction "A1_3") (pintype "input"))
      (node (ref "E7") (pin "4") (pinfunction "A2_4") (pintype "input"))
      (node (ref "R20") (pin "1") (pinfunction "1_1") (pintype "passive"))
    )
    (net (code "11") (name "FEED_HOLE") (class "Default")
      (node (ref "J2") (pin "DD") (pinfunction "P_DD") (pintype "passive"))
      (node (ref "R1") (pin "1") (pinfunction "1_1") (pintype "passive"))
    )
    (net (code "12") (name "GND") (class "Default")
      (node (ref "C1") (pin "2") (pinfunction "2_2") (pintype "passive"))
      (node (ref "C10") (pin "2") (pinfunction "2_2") (pintype "passive"))
      (node (ref "C11") (pin "2") (pinfunction "2_2") (pintype "passive"))
      (node (ref "C12") (pin "2") (pinfunction "2_2") (pintype "passive"))
      (node (ref "C13") (pin "2") (pinfunction "2_2") (pintype "passive"))
      (node (ref "C14") (pin "2") (pinfunction "2_2") (pintype "passive"))
      (node (ref "C15") (pin "2") (pinfunction "2_2") (pintype "passive"))
      (node (ref "C16") (pin "2") (pinfunction "2_2") (pintype "passive"))
      (node (ref "C17") (pin "2") (pinfunction "2_2") (pintype "passive"))
      (node (ref "C18") (pin "2") (pinfunction "2_2") (pintype "passive"))
      (node (ref "C19") (pin "2") (pinfunction "2_2") (pintype "passive"))
      (node (ref "C2") (pin "2") (pinfunction "2_2") (pintype "passive"))
      (node (ref "C20") (pin "2") (pinfunction "2_2") (pintype "passive"))
      (node (ref "C21") (pin "2") (pinfunction "2_2") (pintype "passive"))
      (node (ref "C22") (pin "2") (pinfunction "2_2") (pintype "passive"))
      (node (ref "C23") (pin "2") (pinfunction "2_2") (pintype "passive"))
      (node (ref "C24") (pin "2") (pinfunction "2_2") (pintype "passive"))
      (node (ref "C25") (pin "2") (pinfunction "2_2") (pintype "passive"))
      (node (ref "C26") (pin "2") (pinfunction "2_2") (pintype "passive"))
      (node (ref "C27") (pin "2") (pinfunction "2_2") (pintype "passive"))
      (node (ref "C28") (pin "2") (pinfunction "2_2") (pintype "passive"))
      (node (ref "C29") (pin "2") (pinfunction "2_2") (pintype "passive"))
      (node (ref "C3") (pin "2") (pinfunction "2_2") (pintype "passive"))
      (node (ref "C30") (pin "2") (pinfunction "2_2") (pintype "passive"))
      (node (ref "C31") (pin "-") (pinfunction "-_-") (pintype "passive"))
      (node (ref "C32") (pin "2") (pinfunction "2_2") (pintype "passive"))
      (node (ref "C33") (pin "2") (pinfunction "2_2") (pintype "passive"))
      (node (ref "C34") (pin "2") (pinfunction "2_2") (pintype "passive"))
      (node (ref "C35") (pin "2") (pinfunction "2_2") (pintype "passive"))
      (node (ref "C36") (pin "2") (pinfunction "2_2") (pintype "passive"))
      (node (ref "C37") (pin "2") (pinfunction "2_2") (pintype "passive"))
      (node (ref "C38") (pin "2") (pinfunction "2_2") (pintype "passive"))
      (node (ref "C39") (pin "2") (pinfunction "2_2") (pintype "passive"))
      (node (ref "C4") (pin "2") (pinfunction "2_2") (pintype "passive"))
      (node (ref "C40") (pin "2") (pinfunction "2_2") (pintype "passive"))
      (node (ref "C41") (pin "2") (pinfunction "2_2") (pintype "passive"))
      (node (ref "C42") (pin "2") (pinfunction "2_2") (pintype "passive"))
      (node (ref "C43") (pin "2") (pinfunction "2_2") (pintype "passive"))
      (node (ref "C44") (pin "2") (pinfunction "2_2") (pintype "passive"))
      (node (ref "C45") (pin "-") (pinfunction "-_-") (pintype "passive"))
      (node (ref "C46") (pin "-") (pinfunction "-_-") (pintype "passive"))
      (node (ref "C47") (pin "-") (pinfunction "-_-") (pintype "passive"))
      (node (ref "C48") (pin "-") (pinfunction "-_-") (pintype "passive"))
      (node (ref "C5") (pin "2") (pinfunction "2_2") (pintype "passive"))
      (node (ref "C51") (pin "2") (pinfunction "2_2") (pintype "passive"))
      (node (ref "C55") (pin "2") (pinfunction "2_2") (pintype "passive"))
      (node (ref "C6") (pin "2") (pinfunction "2_2") (pintype "passive"))
      (node (ref "C60") (pin "2") (pinfunction "2_2") (pintype "passive"))
      (node (ref "C61") (pin "2") (pinfunction "2_2") (pintype "passive"))
      (node (ref "C62") (pin "2") (pinfunction "2_2") (pintype "passive"))
      (node (ref "C63") (pin "2") (pinfunction "2_2") (pintype "passive"))
      (node (ref "C64") (pin "2") (pinfunction "2_2") (pintype "passive"))
      (node (ref "C65") (pin "-") (pinfunction "-_-") (pintype "passive"))
      (node (ref "C66") (pin "+") (pinfunction "+_+") (pintype "passive"))
      (node (ref "C7") (pin "2") (pinfunction "2_2") (pintype "passive"))
      (node (ref "C8") (pin "2") (pinfunction "2_2") (pintype "passive"))
      (node (ref "C9") (pin "2") (pinfunction "2_2") (pintype "passive"))
      (node (ref "D4") (pin "A") (pinfunction "A_A") (pintype "passive"))
      (node (ref "D5") (pin "C") (pinfunction "C_C") (pintype "passive"))
      (node (ref "D7") (pin "A") (pinfunction "A_A") (pintype "passive"))
      (node (ref "E10") (pin "2") (pinfunction "D_2") (pintype "input"))
      (node (ref "E12") (pin "2") (pinfunction "D_2") (pintype "input"))
      (node (ref "E15") (pin "3") (pinfunction "A1_3") (pintype "input"))
      (node (ref "E15") (pin "4") (pinfunction "A2_4") (pintype "input"))
      (node (ref "E2") (pin "2") (pinfunction "D_2") (pintype "input"))
      (node (ref "E20") (pin "13") (pinfunction "I_13") (pintype "input"))
      (node (ref "E23") (pin "4") (pinfunction "I0_4") (pintype "input"))
      (node (ref "E23") (pin "5") (pinfunction "I1_5") (pintype "input"))
      (node (ref "E24") (pin "11") (pinfunction "I0_11") (pintype "input"))
      (node (ref "E24") (pin "8") (pinfunction "I0_8") (pintype "input"))
      (node (ref "E24") (pin "9") (pinfunction "I1_9") (pintype "input"))
      (node (ref "E30") (pin "5") (pinfunction "I0_5") (pintype "input"))
      (node (ref "J1") (pin "A") (pinfunction "P_A") (pintype "passive"))
      (node (ref "J1") (pin "AA") (pinfunction "P_AA") (pintype "passive"))
      (node (ref "J1") (pin "B") (pinfunction "P_B") (pintype "passive"))
      (node (ref "J1") (pin "C") (pinfunction "P_C") (pintype "passive"))
      (node (ref "J1") (pin "CC") (pinfunction "P_CC") (pintype "passive"))
      (node (ref "J1") (pin "E") (pinfunction "P_E") (pintype "passive"))
      (node (ref "J1") (pin "EE") (pinfunction "P_EE") (pintype "passive"))
      (node (ref "J1") (pin "H") (pinfunction "P_H") (pintype "passive"))
      (node (ref "J1") (pin "HH") (pinfunction "P_HH") (pintype "passive"))
      (node (ref "J1") (pin "K") (pinfunction "P_K") (pintype "passive"))
      (node (ref "J1") (pin "KK") (pinfunction "P_KK") (pintype "passive"))
      (node (ref "J1") (pin "L") (pinfunction "P_L") (pintype "passive"))
      (node (ref "J1") (pin "M") (pinfunction "P_M") (pintype "passive"))
      (node (ref "J1") (pin "MM") (pinfunction "P_MM") (pintype "passive"))
      (node (ref "J1") (pin "NN") (pinfunction "P_NN") (pintype "passive"))
      (node (ref "J1") (pin "P") (pinfunction "P_P") (pintype "passive"))
      (node (ref "J1") (pin "PP") (pinfunction "P_PP") (pintype "passive"))
      (node (ref "J1") (pin "RR") (pinfunction "P_RR") (pintype "passive"))
      (node (ref "J1") (pin "S") (pinfunction "P_S") (pintype "passive"))
      (node (ref "J1") (pin "SS") (pinfunction "P_SS") (pintype "passive"))
      (node (ref "J1") (pin "TT") (pinfunction "P_TT") (pintype "passive"))
      (node (ref "J1") (pin "U") (pinfunction "P_U") (pintype "passive"))
      (node (ref "J1") (pin "UU") (pinfunction "P_UU") (pintype "passive"))
      (node (ref "J1") (pin "VV") (pinfunction "P_VV") (pintype "passive"))
      (node (ref "J1") (pin "W") (pinfunction "P_W") (pintype "passive"))
      (node (ref "J1") (pin "Y") (pinfunction "P_Y") (pintype "passive"))
      (node (ref "J2") (pin "A") (pinfunction "P_A") (pintype "passive"))
      (node (ref "J2") (pin "AA") (pinfunction "P_AA") (pintype "passive"))
      (node (ref "J2") (pin "B") (pinfunction "P_B") (pintype "passive"))
      (node (ref "J2") (pin "C") (pinfunction "P_C") (pintype "passive"))
      (node (ref "J2") (pin "CC") (pinfunction "P_CC") (pintype "passive"))
      (node (ref "J2") (pin "D") (pinfunction "P_D") (pintype "passive"))
      (node (ref "J2") (pin "E") (pinfunction "P_E") (pintype "passive"))
      (node (ref "J2") (pin "EE") (pinfunction "P_EE") (pintype "passive"))
      (node (ref "J2") (pin "H") (pinfunction "P_H") (pintype "passive"))
      (node (ref "J2") (pin "HH") (pinfunction "P_HH") (pintype "passive"))
      (node (ref "J2") (pin "J") (pinfunction "P_J") (pintype "passive"))
      (node (ref "J2") (pin "K") (pinfunction "P_K") (pintype "passive"))
      (node (ref "J2") (pin "KK") (pinfunction "P_KK") (pintype "passive"))
      (node (ref "J2") (pin "M") (pinfunction "P_M") (pintype "passive"))
      (node (ref "J2") (pin "MM") (pinfunction "P_MM") (pintype "passive"))
      (node (ref "J2") (pin "P") (pinfunction "P_P") (pintype "passive"))
      (node (ref "J2") (pin "PP") (pinfunction "P_PP") (pintype "passive"))
      (node (ref "J2") (pin "S") (pinfunction "P_S") (pintype "passive"))
      (node (ref "J2") (pin "SS") (pinfunction "P_SS") (pintype "passive"))
      (node (ref "J2") (pin "U") (pinfunction "P_U") (pintype "passive"))
      (node (ref "J2") (pin "UU") (pinfunction "P_UU") (pintype "passive"))
      (node (ref "J2") (pin "VV") (pinfunction "P_VV") (pintype "passive"))
      (node (ref "J2") (pin "W") (pinfunction "P_W") (pintype "passive"))
      (node (ref "J2") (pin "Y") (pinfunction "P_Y") (pintype "passive"))
      (node (ref "OMNIBUS") (pin "AC2") (pinfunction "1_AC2") (pintype "bidirectional"))
      (node (ref "OMNIBUS") (pin "AF1") (pinfunction "1_AF1") (pintype "bidirectional"))
      (node (ref "OMNIBUS") (pin "AF2") (pinfunction "1_AF2") (pintype "bidirectional"))
      (node (ref "OMNIBUS") (pin "AN1") (pinfunction "1_AN1") (pintype "bidirectional"))
      (node (ref "OMNIBUS") (pin "AN2") (pinfunction "1_AN2") (pintype "bidirectional"))
      (node (ref "OMNIBUS") (pin "AT1") (pinfunction "1_AT1") (pintype "bidirectional"))
      (node (ref "OMNIBUS") (pin "AT2") (pinfunction "1_AT2") (pintype "bidirectional"))
      (node (ref "OMNIBUS") (pin "BC1") (pinfunction "1_BC1") (pintype "bidirectional"))
      (node (ref "OMNIBUS") (pin "BC2") (pinfunction "1_BC2") (pintype "bidirectional"))
      (node (ref "OMNIBUS") (pin "BF1") (pinfunction "1_BF1") (pintype "bidirectional"))
      (node (ref "OMNIBUS") (pin "BF2") (pinfunction "1_BF2") (pintype "bidirectional"))
      (node (ref "OMNIBUS") (pin "BN1") (pinfunction "1_BN1") (pintype "bidirectional"))
      (node (ref "OMNIBUS") (pin "BN2") (pinfunction "1_BN2") (pintype "bidirectional"))
      (node (ref "OMNIBUS") (pin "BT1") (pinfunction "1_BT1") (pintype "bidirectional"))
      (node (ref "OMNIBUS") (pin "BT2") (pinfunction "1_BT2") (pintype "bidirectional"))
      (node (ref "OMNIBUS") (pin "CC1") (pinfunction "1_CC1") (pintype "bidirectional"))
      (node (ref "OMNIBUS") (pin "CC2") (pinfunction "1_CC2") (pintype "bidirectional"))
      (node (ref "OMNIBUS") (pin "CF1") (pinfunction "1_CF1") (pintype "bidirectional"))
      (node (ref "OMNIBUS") (pin "CF2") (pinfunction "1_CF2") (pintype "bidirectional"))
      (node (ref "OMNIBUS") (pin "CN1") (pinfunction "1_CN1") (pintype "bidirectional"))
      (node (ref "OMNIBUS") (pin "CN2") (pinfunction "1_CN2") (pintype "bidirectional"))
      (node (ref "OMNIBUS") (pin "CT1") (pinfunction "1_CT1") (pintype "bidirectional"))
      (node (ref "OMNIBUS") (pin "CT2") (pinfunction "1_CT2") (pintype "bidirectional"))
      (node (ref "OMNIBUS") (pin "DC1") (pinfunction "1_DC1") (pintype "bidirectional"))
      (node (ref "OMNIBUS") (pin "DC2") (pinfunction "1_DC2") (pintype "bidirectional"))
      (node (ref "OMNIBUS") (pin "DF1") (pinfunction "1_DF1") (pintype "bidirectional"))
      (node (ref "OMNIBUS") (pin "DF2") (pinfunction "1_DF2") (pintype "bidirectional"))
      (node (ref "OMNIBUS") (pin "DN1") (pinfunction "1_DN1") (pintype "bidirectional"))
      (node (ref "OMNIBUS") (pin "DN2") (pinfunction "1_DN2") (pintype "bidirectional"))
      (node (ref "OMNIBUS") (pin "DT1") (pinfunction "1_DT1") (pintype "bidirectional"))
      (node (ref "OMNIBUS") (pin "DT2") (pinfunction "1_DT2") (pintype "bidirectional"))
      (node (ref "R12") (pin "1") (pinfunction "1_1") (pintype "passive"))
      (node (ref "R13") (pin "1") (pinfunction "1_1") (pintype "passive"))
      (node (ref "R27") (pin "3") (pinfunction "E_3") (pintype "passive"))
      (node (ref "R36") (pin "1") (pinfunction "1_1") (pintype "passive"))
      (node (ref "R46") (pin "1") (pinfunction "1_1") (pintype "passive"))
      (node (ref "R5") (pin "1") (pinfunction "1_1") (pintype "passive"))
      (node (ref "R6") (pin "1") (pinfunction "1_1") (pintype "passive"))
    )
    (net (code "13") (name "HAVE_TAPE") (class "Default")
      (node (ref "E11") (pin "10") (pinfunction "I1_10") (pintype "input"))
      (node (ref "E26") (pin "10") (pinfunction "O_10") (pintype "output"))
    )
    (net (code "14") (name "INITIALIZE") (class "Default")
      (node (ref "E30") (pin "6") (pinfunction "I1_6") (pintype "input"))
      (node (ref "OMNIBUS") (pin "CR1") (pinfunction "1_CR1") (pintype "bidirectional"))
    )
    (net (code "15") (name "INT_ENA") (class "Default")
      (node (ref "E14") (pin "5") (pinfunction "Q_5") (pintype "output"))
      (node (ref "E18") (pin "10") (pinfunction "I1_10") (pintype "input"))
      (node (ref "E18") (pin "12") (pinfunction "I0_12") (pintype "input"))
    )
    (net (code "16") (name "IOT01") (class "Default")
      (node (ref "E17") (pin "4") (pinfunction "I0_4") (pintype "input"))
      (node (ref "E17") (pin "5") (pinfunction "I1_5") (pintype "input"))
      (node (ref "E20") (pin "4") (pinfunction "O_4") (pintype "output"))
      (node (ref "E24") (pin "2") (pinfunction "I0_2") (pintype "input"))
      (node (ref "E29") (pin "13") (pinfunction "I_13") (pintype "input"))
    )
    (net (code "17") (name "IOT02") (class "Default")
      (node (ref "E17") (pin "1") (pinfunction "I0_1") (pintype "input"))
      (node (ref "E17") (pin "2") (pinfunction "I1_2") (pintype "input"))
      (node (ref "E20") (pin "8") (pinfunction "O_8") (pintype "output"))
      (node (ref "E24") (pin "3") (pinfunction "I1_3") (pintype "input"))
      (node (ref "E24") (pin "5") (pinfunction "I0_5") (pintype "input"))
      (node (ref "E24") (pin "6") (pinfunction "I1_6") (pintype "input"))
      (node (ref "E29") (pin "5") (pinfunction "I_5") (pintype "input"))
    )
    (net (code "18") (name "MD7") (class "Default")
      (node (ref "E20") (pin "6") (pinfunction "O_6") (pintype "output"))
      (node (ref "E25") (pin "6") (pinfunction "I5_6") (pintype "input"))
    )
    (net (code "19") (name "MD8") (class "Default")
      (node (ref "E20") (pin "2") (pinfunction "O_2") (pintype "output"))
      (node (ref "E21") (pin "11") (pinfunction "I6_11") (pintype "input"))
    )
    (net (code "20") (name "MOTOR_POWER") (class "Default")
      (node (ref "E8") (pin "2") (pinfunction "O_2") (pintype "output"))
      (node (ref "J2") (pin "RR") (pinfunction "P_RR") (pintype "passive"))
    )
    (net (code "21") (name "Net-(C31-Pad+)") (class "Default")
      (node (ref "C31") (pin "+") (pinfunction "+_+") (pintype "passive"))
      (node (ref "C48") (pin "+") (pinfunction "+_+") (pintype "passive"))
      (node (ref "R1") (pin "2") (pinfunction "2_2") (pintype "passive"))
      (node (ref "R2") (pin "1") (pinfunction "1_1") (pintype "passive"))
    )
    (net (code "22") (name "Net-(C59-Pad-)") (class "Default")
      (node (ref "C59") (pin "-") (pinfunction "-_-") (pintype "passive"))
      (node (ref "R44") (pin "1") (pinfunction "1_1") (pintype "passive"))
    )
    (net (code "23") (name "Net-(D1-PadC)") (class "Default")
      (node (ref "D1") (pin "C") (pinfunction "C_C") (pintype "passive"))
      (node (ref "D2") (pin "A") (pinfunction "A_A") (pintype "passive"))
    )
    (net (code "24") (name "Net-(D2-PadC)") (class "Default")
      (node (ref "D2") (pin "C") (pinfunction "C_C") (pintype "passive"))
      (node (ref "D3") (pin "A") (pinfunction "A_A") (pintype "passive"))
    )
    (net (code "25") (name "Net-(D3-PadC)") (class "Default")
      (node (ref "D3") (pin "C") (pinfunction "C_C") (pintype "passive"))
      (node (ref "D5") (pin "A") (pinfunction "A_A") (pintype "passive"))
    )
    (net (code "26") (name "Net-(E1A-O)") (class "Default")
      (node (ref "E1") (pin "12") (pinfunction "O_12") (pintype "output"))
      (node (ref "E8") (pin "3") (pinfunction "I_3") (pintype "input"))
    )
    (net (code "27") (name "Net-(E1B-I1)") (class "Default")
      (node (ref "C62") (pin "1") (pinfunction "1_1") (pintype "passive"))
      (node (ref "E1") (pin "4") (pinfunction "I1_4") (pintype "input"))
      (node (ref "R38") (pin "2") (pinfunction "2_2") (pintype "passive"))
    )
    (net (code "28") (name "Net-(E1B-I2)") (class "Default")
      (node (ref "E1") (pin "5") (pinfunction "I2_5") (pintype "input"))
      (node (ref "E1") (pin "8") (pinfunction "O_8") (pintype "output"))
      (node (ref "E8") (pin "9") (pinfunction "I_9") (pintype "input"))
    )
    (net (code "29") (name "Net-(E1C-I0)") (class "Default")
      (node (ref "E1") (pin "10") (pinfunction "I1_10") (pintype "input"))
      (node (ref "E1") (pin "9") (pinfunction "I0_9") (pintype "input"))
      (node (ref "E3") (pin "10") (pinfunction "O_10") (pintype "output"))
      (node (ref "E5") (pin "1") (pinfunction "I0_1") (pintype "input"))
    )
    (net (code "30") (name "Net-(E1C-I2)") (class "Default")
      (node (ref "C61") (pin "1") (pinfunction "1_1") (pintype "passive"))
      (node (ref "E1") (pin "11") (pinfunction "I2_11") (pintype "input"))
      (node (ref "R35") (pin "2") (pinfunction "2_2") (pintype "passive"))
    )
    (net (code "31") (name "Net-(E2B-PRE)") (class "Default")
      (node (ref "E2") (pin "10") (pinfunction "PRE_10") (pintype "input"))
      (node (ref "E8") (pin "12") (pinfunction "O_12") (pintype "output"))
    )
    (net (code "32") (name "Net-(E2B-~{Q})") (class "Default")
      (node (ref "E2") (pin "8") (pinfunction "~{Q}_8") (pintype "output"))
      (node (ref "E35") (pin "1") (pinfunction "I0_1") (pintype "input"))
      (node (ref "E35") (pin "2") (pinfunction "I1_2") (pintype "input"))
      (node (ref "E5") (pin "12") (pinfunction "I0_12") (pintype "input"))
    )
    (net (code "33") (name "Net-(E3A-I)") (class "Default")
      (node (ref "E3") (pin "1") (pinfunction "I_1") (pintype "input"))
      (node (ref "E6") (pin "10") (pinfunction "I1_10") (pintype "input"))
      (node (ref "E9") (pin "9") (pinfunction "Q_9") (pintype "output"))
    )
    (net (code "34") (name "Net-(E3B-I)") (class "Default")
      (node (ref "E3") (pin "3") (pinfunction "I_3") (pintype "input"))
      (node (ref "E6") (pin "9") (pinfunction "I0_9") (pintype "input"))
      (node (ref "E9") (pin "12") (pinfunction "D_12") (pintype "input"))
      (node (ref "E9") (pin "5") (pinfunction "Q_5") (pintype "output"))
    )
    (net (code "35") (name "Net-(E4A-B)") (class "Default")
      (node (ref "E4") (pin "5") (pinfunction "B_5") (pintype "input"))
      (node (ref "E7") (pin "5") (pinfunction "B_5") (pintype "input"))
      (node (ref "R15") (pin "1") (pinfunction "1_1") (pintype "passive"))
    )
    (net (code "36") (name "Net-(E4A-C)") (class "Default")
      (node (ref "C52") (pin "-") (pinfunction "-_-") (pintype "passive"))
      (node (ref "E4") (pin "10") (pinfunction "C_10") (pintype "input"))
    )
    (net (code "37") (name "Net-(E4A-R{slash}C)") (class "Default")
      (node (ref "C52") (pin "+") (pinfunction "+_+") (pintype "passive"))
      (node (ref "E4") (pin "11") (pinfunction "R/C_11") (pintype "input"))
      (node (ref "R16") (pin "1") (pinfunction "1_1") (pintype "passive"))
    )
    (net (code "38") (name "Net-(E5A-I1)") (class "Default")
      (node (ref "C60") (pin "1") (pinfunction "1_1") (pintype "passive"))
      (node (ref "E5") (pin "2") (pinfunction "I1_2") (pintype "input"))
      (node (ref "R34") (pin "2") (pinfunction "2_2") (pintype "passive"))
    )
    (net (code "39") (name "Net-(E5B-I0)") (class "Default")
      (node (ref "E5") (pin "4") (pinfunction "I0_4") (pintype "input"))
      (node (ref "E5") (pin "8") (pinfunction "O_8") (pintype "output"))
    )
    (net (code "40") (name "Net-(E5B-O)") (class "Default")
      (node (ref "E5") (pin "6") (pinfunction "O_6") (pintype "output"))
      (node (ref "E8") (pin "5") (pinfunction "I_5") (pintype "input"))
    )
    (net (code "41") (name "Net-(E6A-O)") (class "Default")
      (node (ref "E6") (pin "3") (pinfunction "O_3") (pintype "output"))
      (node (ref "E8") (pin "13") (pinfunction "I_13") (pintype "input"))
    )
    (net (code "42") (name "Net-(E6D-I0)") (class "Default")
      (node (ref "C32") (pin "1") (pinfunction "1_1") (pintype "passive"))
      (node (ref "E6") (pin "12") (pinfunction "I0_12") (pintype "input"))
      (node (ref "R18") (pin "2") (pinfunction "2_2") (pintype "passive"))
    )
    (net (code "43") (name "Net-(E6D-I1)") (class "Default")
      (node (ref "E6") (pin "13") (pinfunction "I1_13") (pintype "input"))
      (node (ref "E7") (pin "1") (pinfunction "~{Q}_1") (pintype "output"))
    )
    (net (code "44") (name "Net-(E7A-C)") (class "Default")
      (node (ref "C53") (pin "-") (pinfunction "-_-") (pintype "passive"))
      (node (ref "E7") (pin "10") (pinfunction "C_10") (pintype "input"))
    )
    (net (code "45") (name "Net-(E7A-Q)") (class "Default")
      (node (ref "E7") (pin "6") (pinfunction "Q_6") (pintype "output"))
      (node (ref "R18") (pin "1") (pinfunction "1_1") (pintype "passive"))
    )
    (net (code "46") (name "Net-(E7A-R{slash}C)") (class "Default")
      (node (ref "C53") (pin "+") (pinfunction "+_+") (pintype "passive"))
      (node (ref "E7") (pin "11") (pinfunction "R/C_11") (pintype "input"))
      (node (ref "R17") (pin "1") (pinfunction "1_1") (pintype "passive"))
    )
    (net (code "47") (name "Net-(E8D-O)") (class "Default")
      (node (ref "E8") (pin "8") (pinfunction "O_8") (pintype "output"))
      (node (ref "R38") (pin "1") (pinfunction "1_1") (pintype "passive"))
    )
    (net (code "48") (name "Net-(E9A-CLR)") (class "Default")
      (node (ref "E9") (pin "1") (pinfunction "CLR_1") (pintype "input"))
      (node (ref "E9") (pin "10") (pinfunction "PRE_10") (pintype "input"))
      (node (ref "E9") (pin "13") (pinfunction "CLR_13") (pintype "input"))
      (node (ref "E9") (pin "4") (pinfunction "PRE_4") (pintype "input"))
      (node (ref "R41") (pin "1") (pinfunction "1_1") (pintype "passive"))
    )
    (net (code "49") (name "Net-(E10A-~{Q})") (class "Default")
      (node (ref "E10") (pin "11") (pinfunction "CLK_11") (pintype "input"))
      (node (ref "E10") (pin "6") (pinfunction "~{Q}_6") (pintype "output"))
      (node (ref "E13") (pin "2") (pinfunction "I1_2") (pintype "input"))
    )
    (net (code "50") (name "Net-(E10B-CLR)") (class "Default")
      (node (ref "E10") (pin "13") (pinfunction "CLR_13") (pintype "input"))
      (node (ref "E44") (pin "2") (pinfunction "O_2") (pintype "output"))
    )
    (net (code "51") (name "Net-(E10B-D)") (class "Default")
      (node (ref "E10") (pin "10") (pinfunction "PRE_10") (pintype "input"))
      (node (ref "E10") (pin "12") (pinfunction "D_12") (pintype "input"))
      (node (ref "E14") (pin "2") (pinfunction "D_2") (pintype "input"))
      (node (ref "R14") (pin "1") (pinfunction "1_1") (pintype "passive"))
    )
    (net (code "52") (name "Net-(E11A-O)") (class "Default")
      (node (ref "E11") (pin "12") (pinfunction "O_12") (pintype "output"))
      (node (ref "E2") (pin "12") (pinfunction "D_12") (pintype "input"))
    )
    (net (code "53") (name "Net-(E11B-O)") (class "Default")
      (node (ref "E11") (pin "6") (pinfunction "O_6") (pintype "output"))
      (node (ref "E6") (pin "2") (pinfunction "I1_2") (pintype "input"))
    )
    (net (code "54") (name "Net-(E11C-I2)") (class "Default")
      (node (ref "E11") (pin "11") (pinfunction "I2_11") (pintype "input"))
      (node (ref "E28") (pin "6") (pinfunction "O_6") (pintype "output"))
    )
    (net (code "55") (name "Net-(E12A-~{Q})") (class "Default")
      (node (ref "E12") (pin "6") (pinfunction "~{Q}_6") (pintype "output"))
      (node (ref "E8") (pin "1") (pinfunction "I_1") (pintype "input"))
    )
    (net (code "56") (name "Net-(E12B-CLR)") (class "Default")
      (node (ref "E12") (pin "13") (pinfunction "CLR_13") (pintype "input"))
      (node (ref "E8") (pin "4") (pinfunction "O_4") (pintype "output"))
    )
    (net (code "57") (name "Net-(E12B-PRE)") (class "Default")
      (node (ref "E12") (pin "10") (pinfunction "PRE_10") (pintype "input"))
      (node (ref "R42") (pin "1") (pinfunction "1_1") (pintype "passive"))
    )
    (net (code "58") (name "Net-(E12B-Q)") (class "Default")
      (node (ref "E12") (pin "9") (pinfunction "Q_9") (pintype "output"))
      (node (ref "E18") (pin "4") (pinfunction "I0_4") (pintype "input"))
      (node (ref "E18") (pin "9") (pinfunction "I0_9") (pintype "input"))
    )
    (net (code "59") (name "Net-(E13A-O)") (class "Default")
      (node (ref "E13") (pin "12") (pinfunction "I0_12") (pintype "input"))
      (node (ref "E13") (pin "3") (pinfunction "O_3") (pintype "output"))
    )
    (net (code "60") (name "Net-(E13B-O)") (class "Default")
      (node (ref "E13") (pin "6") (pinfunction "O_6") (pintype "output"))
      (node (ref "E35") (pin "12") (pinfunction "I2_12") (pintype "input"))
      (node (ref "E35") (pin "13") (pinfunction "I3_13") (pintype "input"))
    )
    (net (code "61") (name "Net-(E13C-I0)") (class "Default")
      (node (ref "E13") (pin "9") (pinfunction "I0_9") (pintype "input"))
      (node (ref "E3") (pin "9") (pinfunction "I_9") (pintype "input"))
      (node (ref "E9") (pin "6") (pinfunction "~{Q}_6") (pintype "output"))
    )
    (net (code "62") (name "Net-(E13C-I1)") (class "Default")
      (node (ref "E13") (pin "10") (pinfunction "I1_10") (pintype "input"))
      (node (ref "E3") (pin "5") (pinfunction "I_5") (pintype "input"))
      (node (ref "E9") (pin "2") (pinfunction "D_2") (pintype "input"))
      (node (ref "E9") (pin "8") (pinfunction "~{Q}_8") (pintype "output"))
    )
    (net (code "63") (name "Net-(E13D-O)") (class "Default")
      (node (ref "E13") (pin "11") (pinfunction "O_11") (pintype "output"))
      (node (ref "E14") (pin "12") (pinfunction "D_12") (pintype "input"))
    )
    (net (code "64") (name "Net-(E14A-CLK)") (class "Default")
      (node (ref "E14") (pin "3") (pinfunction "CLK_3") (pintype "input"))
      (node (ref "E22") (pin "8") (pinfunction "O_8") (pintype "output"))
    )
    (net (code "65") (name "Net-(E14A-CLR)") (class "Default")
      (node (ref "E14") (pin "1") (pinfunction "CLR_1") (pintype "input"))
      (node (ref "E22") (pin "6") (pinfunction "O_6") (pintype "output"))
    )
    (net (code "66") (name "Net-(E14B-CLK)") (class "Default")
      (node (ref "E14") (pin "11") (pinfunction "CLK_11") (pintype "input"))
      (node (ref "Q10") (pin "3") (pinfunction "C_3") (pintype "passive"))
      (node (ref "R13") (pin "2") (pinfunction "2_2") (pintype "passive"))
    )
    (net (code "67") (name "Net-(E14B-~{Q})") (class "Default")
      (node (ref "E14") (pin "8") (pinfunction "~{Q}_8") (pintype "output"))
      (node (ref "E15") (pin "5") (pinfunction "B_5") (pintype "input"))
    )
    (net (code "68") (name "Net-(E15A-C)") (class "Default")
      (node (ref "C56") (pin "-") (pinfunction "-_-") (pintype "passive"))
      (node (ref "E15") (pin "10") (pinfunction "C_10") (pintype "input"))
    )
    (net (code "69") (name "Net-(E15A-R{slash}C)") (class "Default")
      (node (ref "C56") (pin "+") (pinfunction "+_+") (pintype "passive"))
      (node (ref "E15") (pin "11") (pinfunction "R/C_11") (pintype "input"))
      (node (ref "R47") (pin "1") (pinfunction "1_1") (pintype "passive"))
      (node (ref "R48") (pin "1") (pinfunction "1_1") (pintype "passive"))
    )
    (net (code "70") (name "Net-(E17D-I0)") (class "Default")
      (node (ref "E17") (pin "12") (pinfunction "I0_12") (pintype "input"))
      (node (ref "E3") (pin "12") (pinfunction "O_12") (pintype "output"))
    )
    (net (code "71") (name "Net-(E17D-I1)") (class "Default")
      (node (ref "E17") (pin "13") (pinfunction "I1_13") (pintype "input"))
      (node (ref "E19") (pin "6") (pinfunction "Q_6") (pintype "output"))
      (node (ref "E23") (pin "9") (pinfunction "I0_9") (pintype "input"))
    )
    (net (code "72") (name "Net-(E17D-O)") (class "Default")
      (node (ref "C54") (pin "-") (pinfunction "-_-") (pintype "passive"))
      (node (ref "E17") (pin "11") (pinfunction "O_11") (pintype "open_collector"))
      (node (ref "E19") (pin "10") (pinfunction "C_10") (pintype "input"))
    )
    (net (code "73") (name "Net-(E19A-A1)") (class "Default")
      (node (ref "E19") (pin "3") (pinfunction "A1_3") (pintype "input"))
      (node (ref "E19") (pin "4") (pinfunction "A2_4") (pintype "input"))
      (node (ref "E23") (pin "1") (pinfunction "I0_1") (pintype "input"))
      (node (ref "E23") (pin "13") (pinfunction "I1_13") (pintype "input"))
      (node (ref "E26") (pin "2") (pinfunction "O_2") (pintype "output"))
    )
    (net (code "74") (name "Net-(E19A-B)") (class "Default")
      (node (ref "E19") (pin "5") (pinfunction "B_5") (pintype "input"))
      (node (ref "R52") (pin "1") (pinfunction "1_1") (pintype "passive"))
    )
    (net (code "75") (name "Net-(E19A-R{slash}C)") (class "Default")
      (node (ref "C54") (pin "+") (pinfunction "+_+") (pintype "passive"))
      (node (ref "E19") (pin "11") (pinfunction "R/C_11") (pintype "input"))
      (node (ref "R30") (pin "1") (pinfunction "1_1") (pintype "passive"))
    )
    (net (code "76") (name "Net-(E20B-I)") (class "Default")
      (node (ref "E20") (pin "3") (pinfunction "I_3") (pintype "input"))
      (node (ref "E21") (pin "8") (pinfunction "O_8") (pintype "output"))
    )
    (net (code "77") (name "Net-(E20D-I)") (class "Default")
      (node (ref "E20") (pin "9") (pinfunction "I_9") (pintype "input"))
      (node (ref "E25") (pin "8") (pinfunction "O_8") (pintype "output"))
    )
    (net (code "78") (name "Net-(E23A-I1)") (class "Default")
      (node (ref "E23") (pin "2") (pinfunction "I1_2") (pintype "input"))
      (node (ref "E3") (pin "13") (pinfunction "I_13") (pintype "input"))
      (node (ref "E35") (pin "6") (pinfunction "O_6") (pintype "output"))
    )
    (net (code "79") (name "Net-(E23A-O)") (class "Default")
      (node (ref "E23") (pin "3") (pinfunction "O_3") (pintype "output"))
      (node (ref "E35") (pin "4") (pinfunction "I2_4") (pintype "input"))
      (node (ref "E35") (pin "5") (pinfunction "I3_5") (pintype "input"))
    )
    (net (code "80") (name "Net-(E23D-I0)") (class "Default")
      (node (ref "C22") (pin "1") (pinfunction "1_1") (pintype "passive"))
      (node (ref "E23") (pin "12") (pinfunction "I0_12") (pintype "input"))
      (node (ref "R51") (pin "2") (pinfunction "2_2") (pintype "passive"))
    )
    (net (code "81") (name "Net-(E23D-O)") (class "Default")
      (node (ref "E23") (pin "11") (pinfunction "O_11") (pintype "output"))
      (node (ref "R29") (pin "1") (pinfunction "1_1") (pintype "passive"))
    )
    (net (code "82") (name "Net-(E24A-O)") (class "Default")
      (node (ref "E24") (pin "1") (pinfunction "O_1") (pintype "output"))
      (node (ref "E30") (pin "11") (pinfunction "I0_11") (pintype "input"))
      (node (ref "E30") (pin "3") (pinfunction "I1_3") (pintype "input"))
      (node (ref "E30") (pin "9") (pinfunction "I1_9") (pintype "input"))
    )
    (net (code "83") (name "Net-(E24D-O)") (class "Default")
      (node (ref "E24") (pin "13") (pinfunction "O_13") (pintype "output"))
      (node (ref "E26") (pin "9") (pinfunction "I_9") (pintype "input"))
    )
    (net (code "84") (name "Net-(E26A-I)") (class "Default")
      (node (ref "E26") (pin "1") (pinfunction "I_1") (pintype "input"))
      (node (ref "Q7") (pin "3") (pinfunction "C_3") (pintype "passive"))
      (node (ref "Q8") (pin "2") (pinfunction "B_2") (pintype "passive"))
      (node (ref "R3") (pin "1") (pinfunction "1_1") (pintype "passive"))
    )
    (net (code "85") (name "Net-(E26C-O)") (class "Default")
      (node (ref "E26") (pin "6") (pinfunction "O_6") (pintype "output"))
      (node (ref "IC37") (pin "9") (pinfunction "CLK_9") (pintype "input"))
      (node (ref "IC43") (pin "9") (pinfunction "CLK_9") (pintype "input"))
    )
    (net (code "86") (name "Net-(E27A-A)") (class "Default")
      (node (ref "E27") (pin "1") (pinfunction "A_1") (pintype "input"))
      (node (ref "E30") (pin "1") (pinfunction "O_1") (pintype "output"))
      (node (ref "E31") (pin "1") (pinfunction "A_1") (pintype "input"))
    )
    (net (code "87") (name "Net-(E27A-B)") (class "Default")
      (node (ref "E27") (pin "2") (pinfunction "B_2") (pintype "input"))
      (node (ref "E30") (pin "10") (pinfunction "O_10") (pintype "output"))
      (node (ref "E31") (pin "2") (pinfunction "B_2") (pintype "input"))
    )
    (net (code "88") (name "Net-(E27A-C)") (class "Default")
      (node (ref "E27") (pin "3") (pinfunction "C_3") (pintype "input"))
      (node (ref "E30") (pin "13") (pinfunction "O_13") (pintype "output"))
      (node (ref "E31") (pin "3") (pinfunction "C_3") (pintype "input"))
    )
    (net (code "89") (name "Net-(E27A-G2A)") (class "Default")
      (node (ref "E27") (pin "4") (pinfunction "G2A_4") (pintype "input"))
      (node (ref "E27") (pin "5") (pinfunction "G2B_5") (pintype "input"))
      (node (ref "E29") (pin "6") (pinfunction "O_6") (pintype "output"))
      (node (ref "R28") (pin "1") (pinfunction "1_1") (pintype "passive"))
    )
    (net (code "90") (name "Net-(E29F-O)") (class "Default")
      (node (ref "E29") (pin "12") (pinfunction "O_12") (pintype "output"))
      (node (ref "E31") (pin "4") (pinfunction "G2A_4") (pintype "input"))
      (node (ref "E31") (pin "5") (pinfunction "G2B_5") (pintype "input"))
    )
    (net (code "91") (name "Net-(E32A-I0)") (class "Default")
      (node (ref "E32") (pin "1") (pinfunction "I0_1") (pintype "input"))
      (node (ref "E32") (pin "11") (pinfunction "O_11") (pintype "output"))
      (node (ref "R51") (pin "1") (pinfunction "1_1") (pintype "passive"))
    )
    (net (code "92") (name "Net-(E32A-I1)") (class "Default")
      (node (ref "C55") (pin "1") (pinfunction "1_1") (pintype "passive"))
      (node (ref "E32") (pin "2") (pinfunction "I1_2") (pintype "input"))
      (node (ref "E44") (pin "3") (pinfunction "I_3") (pintype "input"))
      (node (ref "R29") (pin "2") (pinfunction "2_2") (pintype "passive"))
    )
    (net (code "93") (name "Net-(E32A-O)") (class "Default")
      (node (ref "E32") (pin "13") (pinfunction "I1_13") (pintype "input"))
      (node (ref "E32") (pin "3") (pinfunction "O_3") (pintype "output"))
    )
    (net (code "94") (name "Net-(E32B-O)") (class "Default")
      (node (ref "E32") (pin "10") (pinfunction "I1_10") (pintype "input"))
      (node (ref "E32") (pin "6") (pinfunction "O_6") (pintype "output"))
    )
    (net (code "95") (name "Net-(E32C-O)") (class "Default")
      (node (ref "E32") (pin "12") (pinfunction "I0_12") (pintype "input"))
      (node (ref "E32") (pin "8") (pinfunction "O_8") (pintype "output"))
    )
    (net (code "96") (name "Net-(E33A-I0)") (class "Default")
      (node (ref "E33") (pin "1") (pinfunction "I0_1") (pintype "input"))
      (node (ref "IC34") (pin "2") (pinfunction "Q1_2") (pintype "output"))
    )
    (net (code "97") (name "Net-(E33B-I0)") (class "Default")
      (node (ref "E33") (pin "4") (pinfunction "I0_4") (pintype "input"))
      (node (ref "IC34") (pin "7") (pinfunction "Q2_7") (pintype "output"))
    )
    (net (code "98") (name "Net-(E33C-I1)") (class "Default")
      (node (ref "E33") (pin "10") (pinfunction "I1_10") (pintype "input"))
      (node (ref "IC34") (pin "15") (pinfunction "Q4_15") (pintype "output"))
    )
    (net (code "99") (name "Net-(E33D-I1)") (class "Default")
      (node (ref "E33") (pin "13") (pinfunction "I1_13") (pintype "input"))
      (node (ref "IC34") (pin "10") (pinfunction "Q3_10") (pintype "output"))
    )
    (net (code "100") (name "Net-(E35D-O)") (class "Default")
      (node (ref "E35") (pin "8") (pinfunction "O_8") (pintype "output"))
      (node (ref "E44") (pin "1") (pinfunction "I_1") (pintype "input"))
    )
    (net (code "101") (name "Net-(E36A-O)") (class "Default")
      (node (ref "E36") (pin "1") (pinfunction "O_1") (pintype "output"))
      (node (ref "IC37") (pin "4") (pinfunction "D1_4") (pintype "input"))
    )
    (net (code "102") (name "Net-(E36B-O)") (class "Default")
      (node (ref "E36") (pin "4") (pinfunction "O_4") (pintype "output"))
      (node (ref "IC37") (pin "5") (pinfunction "D2_5") (pintype "input"))
    )
    (net (code "103") (name "Net-(E36C-O)") (class "Default")
      (node (ref "E36") (pin "10") (pinfunction "O_10") (pintype "output"))
      (node (ref "IC37") (pin "13") (pinfunction "D4_13") (pintype "input"))
    )
    (net (code "104") (name "Net-(E36D-O)") (class "Default")
      (node (ref "E36") (pin "13") (pinfunction "O_13") (pintype "output"))
      (node (ref "IC37") (pin "12") (pinfunction "D3_12") (pintype "input"))
    )
    (net (code "105") (name "Net-(E38A-I)") (class "Default")
      (node (ref "E38") (pin "1") (pinfunction "I_1") (pintype "input"))
      (node (ref "E38") (pin "8") (pinfunction "O_8") (pintype "output"))
    )
    (net (code "106") (name "Net-(E38B-I)") (class "Default")
      (node (ref "E38") (pin "3") (pinfunction "I_3") (pintype "input"))
      (node (ref "IC37") (pin "2") (pinfunction "Q1_2") (pintype "output"))
    )
    (net (code "107") (name "Net-(E38B-O)") (class "Default")
      (node (ref "E38") (pin "4") (pinfunction "O_4") (pintype "output"))
      (node (ref "E41") (pin "5") (pinfunction "I_5") (pintype "input"))
    )
    (net (code "108") (name "Net-(E38C-I)") (class "Default")
      (node (ref "E38") (pin "5") (pinfunction "I_5") (pintype "input"))
      (node (ref "IC37") (pin "7") (pinfunction "Q2_7") (pintype "output"))
    )
    (net (code "109") (name "Net-(E38C-O)") (class "Default")
      (node (ref "E38") (pin "6") (pinfunction "O_6") (pintype "output"))
      (node (ref "E41") (pin "9") (pinfunction "I_9") (pintype "input"))
    )
    (net (code "110") (name "Net-(E38D-I)") (class "Default")
      (node (ref "E38") (pin "9") (pinfunction "I_9") (pintype "input"))
      (node (ref "IC37") (pin "15") (pinfunction "Q4_15") (pintype "output"))
    )
    (net (code "111") (name "Net-(E38E-I)") (class "Default")
      (node (ref "E38") (pin "11") (pinfunction "I_11") (pintype "input"))
      (node (ref "IC37") (pin "10") (pinfunction "Q3_10") (pintype "output"))
    )
    (net (code "112") (name "Net-(E38E-O)") (class "Default")
      (node (ref "E38") (pin "10") (pinfunction "O_10") (pintype "output"))
      (node (ref "E38") (pin "13") (pinfunction "I_13") (pintype "input"))
    )
    (net (code "113") (name "Net-(E39A-I0)") (class "Default")
      (node (ref "E39") (pin "1") (pinfunction "I0_1") (pintype "input"))
      (node (ref "IC40") (pin "2") (pinfunction "Q1_2") (pintype "output"))
    )
    (net (code "114") (name "Net-(E39B-I1)") (class "Default")
      (node (ref "E39") (pin "5") (pinfunction "I1_5") (pintype "input"))
      (node (ref "IC40") (pin "7") (pinfunction "Q2_7") (pintype "output"))
    )
    (net (code "115") (name "Net-(E39C-I0)") (class "Default")
      (node (ref "E39") (pin "9") (pinfunction "I0_9") (pintype "input"))
      (node (ref "IC40") (pin "10") (pinfunction "Q3_10") (pintype "output"))
    )
    (net (code "116") (name "Net-(E39D-I1)") (class "Default")
      (node (ref "E39") (pin "13") (pinfunction "I1_13") (pintype "input"))
      (node (ref "IC40") (pin "15") (pinfunction "Q4_15") (pintype "output"))
    )
    (net (code "117") (name "Net-(E41A-I)") (class "Default")
      (node (ref "E41") (pin "1") (pinfunction "I_1") (pintype "input"))
      (node (ref "E44") (pin "10") (pinfunction "O_10") (pintype "output"))
    )
    (net (code "118") (name "Net-(E41B-I)") (class "Default")
      (node (ref "E41") (pin "3") (pinfunction "I_3") (pintype "input"))
      (node (ref "E44") (pin "12") (pinfunction "O_12") (pintype "output"))
    )
    (net (code "119") (name "Net-(E41E-I)") (class "Default")
      (node (ref "E41") (pin "11") (pinfunction "I_11") (pintype "input"))
      (node (ref "E44") (pin "8") (pinfunction "O_8") (pintype "output"))
    )
    (net (code "120") (name "Net-(E41F-I)") (class "Default")
      (node (ref "E41") (pin "13") (pinfunction "I_13") (pintype "input"))
      (node (ref "E44") (pin "6") (pinfunction "O_6") (pintype "output"))
    )
    (net (code "121") (name "Net-(E42A-O)") (class "Default")
      (node (ref "E42") (pin "1") (pinfunction "O_1") (pintype "output"))
      (node (ref "IC43") (pin "4") (pinfunction "D1_4") (pintype "input"))
    )
    (net (code "122") (name "Net-(E42B-O)") (class "Default")
      (node (ref "E42") (pin "4") (pinfunction "O_4") (pintype "output"))
      (node (ref "IC43") (pin "5") (pinfunction "D2_5") (pintype "input"))
    )
    (net (code "123") (name "Net-(E42C-O)") (class "Default")
      (node (ref "E42") (pin "10") (pinfunction "O_10") (pintype "output"))
      (node (ref "IC43") (pin "13") (pinfunction "D4_13") (pintype "input"))
    )
    (net (code "124") (name "Net-(E42D-O)") (class "Default")
      (node (ref "E42") (pin "13") (pinfunction "O_13") (pintype "output"))
      (node (ref "IC43") (pin "12") (pinfunction "D3_12") (pintype "input"))
    )
    (net (code "125") (name "Net-(E44C-I)") (class "Default")
      (node (ref "E44") (pin "5") (pinfunction "I_5") (pintype "input"))
      (node (ref "IC43") (pin "2") (pinfunction "Q1_2") (pintype "output"))
    )
    (net (code "126") (name "Net-(E44D-I)") (class "Default")
      (node (ref "E44") (pin "9") (pinfunction "I_9") (pintype "input"))
      (node (ref "IC43") (pin "7") (pinfunction "Q2_7") (pintype "output"))
    )
    (net (code "127") (name "Net-(E44E-I)") (class "Default")
      (node (ref "E44") (pin "11") (pinfunction "I_11") (pintype "input"))
      (node (ref "IC43") (pin "15") (pinfunction "Q4_15") (pintype "output"))
    )
    (net (code "128") (name "Net-(E44F-I)") (class "Default")
      (node (ref "E44") (pin "13") (pinfunction "I_13") (pintype "input"))
      (node (ref "IC43") (pin "10") (pinfunction "Q3_10") (pintype "output"))
    )
    (net (code "129") (name "Net-(IC34A-CLR)") (class "Default")
      (node (ref "IC34") (pin "1") (pinfunction "CLR_1") (pintype "input"))
      (node (ref "IC40") (pin "1") (pinfunction "CLR_1") (pintype "input"))
      (node (ref "R43") (pin "1") (pinfunction "1_1") (pintype "passive"))
    )
    (net (code "130") (name "Net-(Q1-B)") (class "Default")
      (node (ref "Q1") (pin "2") (pinfunction "B_2") (pintype "passive"))
      (node (ref "R20") (pin "2") (pinfunction "2_2") (pintype "passive"))
    )
    (net (code "131") (name "Net-(Q1-C)") (class "Default")
      (node (ref "Q1") (pin "3") (pinfunction "C_3") (pintype "passive"))
      (node (ref "R21") (pin "2") (pinfunction "2_2") (pintype "passive"))
    )
    (net (code "132") (name "Net-(Q2-B)") (class "Default")
      (node (ref "C57") (pin "-") (pinfunction "-_-") (pintype "passive"))
      (node (ref "Q2") (pin "2") (pinfunction "B_2") (pintype "passive"))
      (node (ref "R21") (pin "1") (pinfunction "1_1") (pintype "passive"))
      (node (ref "R22") (pin "1") (pinfunction "1_1") (pintype "passive"))
      (node (ref "R50") (pin "2") (pinfunction "2_2") (pintype "passive"))
    )
    (net (code "133") (name "Net-(Q2-E)") (class "Default")
      (node (ref "Q2") (pin "1") (pinfunction "E_1") (pintype "passive"))
      (node (ref "R19") (pin "1") (pinfunction "1_1") (pintype "passive"))
      (node (ref "R26") (pin "1") (pinfunction "1_1") (pintype "passive"))
      (node (ref "R31") (pin "1") (pinfunction "1_1") (pintype "passive"))
      (node (ref "W1") (pin "1") (pinfunction "1_1") (pintype "passive"))
      (node (ref "W2") (pin "1") (pinfunction "1_1") (pintype "passive"))
    )
    (net (code "134") (name "Net-(Q3-B)") (class "Default")
      (node (ref "Q3") (pin "2") (pinfunction "B_2") (pintype "passive"))
      (node (ref "R23") (pin "2") (pinfunction "2_2") (pintype "passive"))
    )
    (net (code "135") (name "Net-(Q3-C)") (class "Default")
      (node (ref "C58") (pin "-") (pinfunction "-_-") (pintype "passive"))
      (node (ref "D4") (pin "C") (pinfunction "C_C") (pintype "passive"))
      (node (ref "Q3") (pin "3") (pinfunction "C_3") (pintype "passive"))
      (node (ref "R24") (pin "2") (pinfunction "2_2") (pintype "passive"))
    )
    (net (code "136") (name "Net-(Q3-E)") (class "Default")
      (node (ref "Q3") (pin "1") (pinfunction "E_1") (pintype "passive"))
      (node (ref "Q4") (pin "3") (pinfunction "C_3") (pintype "passive"))
    )
    (net (code "137") (name "Net-(Q4-B)") (class "Default")
      (node (ref "C59") (pin "+") (pinfunction "+_+") (pintype "passive"))
      (node (ref "Q4") (pin "2") (pinfunction "B_2") (pintype "passive"))
      (node (ref "R45") (pin "2") (pinfunction "2_2") (pintype "passive"))
    )
    (net (code "138") (name "Net-(Q5-B)") (class "Default")
      (node (ref "C58") (pin "+") (pinfunction "+_+") (pintype "passive"))
      (node (ref "Q5") (pin "2") (pinfunction "B_2") (pintype "passive"))
      (node (ref "R25") (pin "2") (pinfunction "2_2") (pintype "passive"))
    )
    (net (code "139") (name "Net-(Q5-C)") (class "Default")
      (node (ref "D6") (pin "A") (pinfunction "A_A") (pintype "passive"))
      (node (ref "D7") (pin "C") (pinfunction "C_C") (pintype "passive"))
      (node (ref "Q5") (pin "3") (pinfunction "C_3") (pintype "passive"))
      (node (ref "Q6") (pin "2") (pinfunction "B_2") (pintype "passive"))
      (node (ref "R32") (pin "2") (pinfunction "2_2") (pintype "passive"))
    )
    (net (code "140") (name "Net-(Q7-B)") (class "Default")
      (node (ref "Q7") (pin "2") (pinfunction "B_2") (pintype "passive"))
      (node (ref "R2") (pin "2") (pinfunction "2_2") (pintype "passive"))
    )
    (net (code "141") (name "Net-(Q7-E)") (class "Default")
      (node (ref "Q7") (pin "1") (pinfunction "E_1") (pintype "passive"))
      (node (ref "Q8") (pin "1") (pinfunction "E_1") (pintype "passive"))
      (node (ref "R5") (pin "2") (pinfunction "2_2") (pintype "passive"))
    )
    (net (code "142") (name "Net-(Q8-C)") (class "Default")
      (node (ref "Q8") (pin "3") (pinfunction "C_3") (pintype "passive"))
      (node (ref "R4") (pin "1") (pinfunction "1_1") (pintype "passive"))
    )
    (net (code "143") (name "Net-(Q9-B)") (class "Default")
      (node (ref "C50") (pin "2") (pinfunction "2_2") (pintype "passive"))
      (node (ref "Q9") (pin "2") (pinfunction "B_2") (pintype "passive"))
      (node (ref "R11") (pin "2") (pinfunction "2_2") (pintype "passive"))
    )
    (net (code "144") (name "Net-(Q10-B)") (class "Default")
      (node (ref "Q10") (pin "2") (pinfunction "B_2") (pintype "passive"))
      (node (ref "Q9") (pin "3") (pinfunction "C_3") (pintype "passive"))
      (node (ref "R12") (pin "2") (pinfunction "2_2") (pintype "passive"))
      (node (ref "R9") (pin "1") (pinfunction "1_1") (pintype "passive"))
    )
    (net (code "145") (name "Net-(Q10-E)") (class "Default")
      (node (ref "Q10") (pin "1") (pinfunction "E_1") (pintype "passive"))
      (node (ref "Q9") (pin "1") (pinfunction "E_1") (pintype "passive"))
      (node (ref "R8") (pin "1") (pinfunction "1_1") (pintype "passive"))
    )
    (net (code "146") (name "Net-(R25-Pad1)") (class "Default")
      (node (ref "R25") (pin "1") (pinfunction "1_1") (pintype "passive"))
      (node (ref "R26") (pin "2") (pinfunction "2_2") (pintype "passive"))
      (node (ref "W1") (pin "2") (pinfunction "2_2") (pintype "passive"))
    )
    (net (code "147") (name "Net-(R27-S)") (class "Default")
      (node (ref "R27") (pin "2") (pinfunction "S_2") (pintype "passive"))
      (node (ref "R50") (pin "1") (pinfunction "1_1") (pintype "passive"))
    )
    (net (code "148") (name "Net-(R31-Pad2)") (class "Default")
      (node (ref "R31") (pin "2") (pinfunction "2_2") (pintype "passive"))
      (node (ref "R45") (pin "1") (pinfunction "1_1") (pintype "passive"))
      (node (ref "W2") (pin "2") (pinfunction "2_2") (pintype "passive"))
    )
    (net (code "149") (name "OUT_OF_TAPE") (class "Default")
      (node (ref "E23") (pin "8") (pinfunction "O_8") (pintype "output"))
      (node (ref "E26") (pin "11") (pinfunction "I_11") (pintype "input"))
      (node (ref "E5") (pin "9") (pinfunction "I0_9") (pintype "input"))
    )
    (net (code "150") (name "PAUSE") (class "Default")
      (node (ref "E20") (pin "10") (pinfunction "O_10") (pintype "output"))
      (node (ref "E21") (pin "12") (pinfunction "I7_12") (pintype "input"))
      (node (ref "E25") (pin "12") (pinfunction "I7_12") (pintype "input"))
    )
    (net (code "151") (name "PIOP0") (class "Default")
      (node (ref "E22") (pin "5") (pinfunction "I1_5") (pintype "input"))
      (node (ref "E29") (pin "8") (pinfunction "O_8") (pintype "output"))
    )
    (net (code "152") (name "PIOP1") (class "Default")
      (node (ref "E18") (pin "1") (pinfunction "I0_1") (pintype "input"))
      (node (ref "E29") (pin "10") (pinfunction "O_10") (pintype "output"))
    )
    (net (code "153") (name "PIOP2") (class "Default")
      (node (ref "E13") (pin "5") (pinfunction "I1_5") (pintype "input"))
      (node (ref "E28") (pin "8") (pinfunction "O_8") (pintype "output"))
    )
    (net (code "154") (name "PIOP4") (class "Default")
      (node (ref "E22") (pin "13") (pinfunction "I1_13") (pintype "input"))
      (node (ref "E28") (pin "11") (pinfunction "O_11") (pintype "output"))
    )
    (net (code "155") (name "PLS") (class "Default")
      (node (ref "E27") (pin "14") (pinfunction "Y1_14") (pintype "output"))
      (node (ref "E28") (pin "10") (pinfunction "I1_10") (pintype "input"))
      (node (ref "E28") (pin "12") (pinfunction "I0_12") (pintype "input"))
      (node (ref "OMNIBUS") (pin "DB1") (pinfunction "1_DB1") (pintype "bidirectional"))
    )
    (net (code "156") (name "PN_HOLE1") (class "Default")
      (node (ref "E41") (pin "12") (pinfunction "O_12") (pintype "output"))
      (node (ref "J1") (pin "LL") (pinfunction "P_LL") (pintype "passive"))
    )
    (net (code "157") (name "PN_HOLE2") (class "Default")
      (node (ref "E41") (pin "10") (pinfunction "O_10") (pintype "output"))
      (node (ref "J1") (pin "JJ") (pinfunction "P_JJ") (pintype "passive"))
    )
    (net (code "158") (name "PN_HOLE3") (class "Default")
      (node (ref "E41") (pin "2") (pinfunction "O_2") (pintype "output"))
      (node (ref "J1") (pin "FF") (pinfunction "P_FF") (pintype "passive"))
    )
    (net (code "159") (name "PN_HOLE4") (class "Default")
      (node (ref "E41") (pin "4") (pinfunction "O_4") (pintype "output"))
      (node (ref "J1") (pin "DD") (pinfunction "P_DD") (pintype "passive"))
    )
    (net (code "160") (name "PN_HOLE5") (class "Default")
      (node (ref "E41") (pin "6") (pinfunction "O_6") (pintype "output"))
      (node (ref "J1") (pin "Z") (pinfunction "P_Z") (pintype "passive"))
    )
    (net (code "161") (name "PN_HOLE6") (class "Default")
      (node (ref "E41") (pin "8") (pinfunction "O_8") (pintype "output"))
      (node (ref "J1") (pin "X") (pinfunction "P_X") (pintype "passive"))
    )
    (net (code "162") (name "PN_HOLE7") (class "Default")
      (node (ref "E38") (pin "2") (pinfunction "O_2") (pintype "output"))
      (node (ref "J1") (pin "V") (pinfunction "P_V") (pintype "passive"))
    )
    (net (code "163") (name "PN_HOLE8") (class "Default")
      (node (ref "E38") (pin "12") (pinfunction "O_12") (pintype "output"))
      (node (ref "J1") (pin "T") (pinfunction "P_T") (pintype "passive"))
    )
    (net (code "164") (name "PUNCH_DONE") (class "Default")
      (node (ref "E26") (pin "12") (pinfunction "O_12") (pintype "output"))
      (node (ref "J1") (pin "N") (pinfunction "P_N") (pintype "passive"))
    )
    (net (code "165") (name "PUNCH_FLAG") (class "Default")
      (node (ref "E10") (pin "9") (pinfunction "Q_9") (pintype "output"))
      (node (ref "E18") (pin "13") (pinfunction "I1_13") (pintype "input"))
      (node (ref "E18") (pin "2") (pinfunction "I1_2") (pintype "input"))
    )
    (net (code "166") (name "PUNCH_SYNC") (class "Default")
      (node (ref "J1") (pin "J") (pinfunction "P_J") (pintype "passive"))
      (node (ref "R11") (pin "1") (pinfunction "1_1") (pintype "passive"))
    )
    (net (code "167") (name "PUN_TO_SPEED") (class "Default")
      (node (ref "E13") (pin "13") (pinfunction "I1_13") (pintype "input"))
      (node (ref "J1") (pin "R") (pinfunction "P_R") (pintype "passive"))
      (node (ref "R36") (pin "2") (pinfunction "2_2") (pintype "passive"))
      (node (ref "R37") (pin "2") (pinfunction "2_2") (pintype "passive"))
    )
    (net (code "168") (name "RDATA_STROBE") (class "Default")
      (node (ref "E12") (pin "11") (pinfunction "CLK_11") (pintype "input"))
      (node (ref "E2") (pin "3") (pinfunction "CLK_3") (pintype "input"))
      (node (ref "E44") (pin "4") (pinfunction "O_4") (pintype "output"))
      (node (ref "IC34") (pin "9") (pinfunction "CLK_9") (pintype "input"))
      (node (ref "IC40") (pin "9") (pinfunction "CLK_9") (pintype "input"))
    )
    (net (code "169") (name "RDATA_TO_BUS") (class "Default")
      (node (ref "E17") (pin "10") (pinfunction "I1_10") (pintype "input"))
      (node (ref "E17") (pin "9") (pinfunction "I0_9") (pintype "input"))
      (node (ref "E22") (pin "1") (pinfunction "I0_1") (pintype "input"))
      (node (ref "E28") (pin "3") (pinfunction "O_3") (pintype "output"))
      (node (ref "E33") (pin "12") (pinfunction "I0_12") (pintype "input"))
      (node (ref "E33") (pin "2") (pinfunction "I1_2") (pintype "input"))
      (node (ref "E33") (pin "5") (pinfunction "I1_5") (pintype "input"))
      (node (ref "E33") (pin "9") (pinfunction "I0_9") (pintype "input"))
      (node (ref "E39") (pin "10") (pinfunction "I1_10") (pintype "input"))
      (node (ref "E39") (pin "12") (pinfunction "I0_12") (pintype "input"))
      (node (ref "E39") (pin "2") (pinfunction "I1_2") (pintype "input"))
      (node (ref "E39") (pin "4") (pinfunction "I0_4") (pintype "input"))
      (node (ref "OMNIBUS") (pin "DA1") (pinfunction "1_DA1") (pintype "bidirectional"))
    )
    (net (code "170") (name "RDR_RUN") (class "Default")
      (node (ref "E11") (pin "4") (pinfunction "I1_4") (pintype "input"))
      (node (ref "E12") (pin "12") (pinfunction "D_12") (pintype "input"))
      (node (ref "E2") (pin "5") (pinfunction "Q_5") (pintype "output"))
    )
    (net (code "171") (name "RD_HOLE1") (class "Default")
      (node (ref "IC40") (pin "13") (pinfunction "D4_13") (pintype "input"))
      (node (ref "J2") (pin "L") (pinfunction "P_L") (pintype "passive"))
    )
    (net (code "172") (name "RD_HOLE2") (class "Default")
      (node (ref "IC40") (pin "12") (pinfunction "D3_12") (pintype "input"))
      (node (ref "J2") (pin "N") (pinfunction "P_N") (pintype "passive"))
    )
    (net (code "173") (name "RD_HOLE3") (class "Default")
      (node (ref "IC40") (pin "5") (pinfunction "D2_5") (pintype "input"))
      (node (ref "J2") (pin "R") (pinfunction "P_R") (pintype "passive"))
    )
    (net (code "174") (name "RD_HOLE4") (class "Default")
      (node (ref "IC40") (pin "4") (pinfunction "D1_4") (pintype "input"))
      (node (ref "J2") (pin "T") (pinfunction "P_T") (pintype "passive"))
    )
    (net (code "175") (name "RD_HOLE5") (class "Default")
      (node (ref "IC34") (pin "13") (pinfunction "D4_13") (pintype "input"))
      (node (ref "J2") (pin "V") (pinfunction "P_V") (pintype "passive"))
    )
    (net (code "176") (name "RD_HOLE6") (class "Default")
      (node (ref "IC34") (pin "12") (pinfunction "D3_12") (pintype "input"))
      (node (ref "J2") (pin "X") (pinfunction "P_X") (pintype "passive"))
    )
    (net (code "177") (name "RD_HOLE7") (class "Default")
      (node (ref "IC34") (pin "5") (pinfunction "D2_5") (pintype "input"))
      (node (ref "J2") (pin "Z") (pinfunction "P_Z") (pintype "passive"))
    )
    (net (code "178") (name "RD_HOLE8") (class "Default")
      (node (ref "IC34") (pin "4") (pinfunction "D1_4") (pintype "input"))
      (node (ref "J2") (pin "BB") (pinfunction "P_BB") (pintype "passive"))
    )
    (net (code "179") (name "RIOP0") (class "Default")
      (node (ref "E22") (pin "9") (pinfunction "I0_9") (pintype "input"))
      (node (ref "E29") (pin "4") (pinfunction "O_4") (pintype "output"))
    )
    (net (code "180") (name "RIOP1") (class "Default")
      (node (ref "E18") (pin "5") (pinfunction "I1_5") (pintype "input"))
      (node (ref "E29") (pin "2") (pinfunction "O_2") (pintype "output"))
    )
    (net (code "181") (name "ROTATE_PULSE") (class "Default")
      (node (ref "E6") (pin "6") (pinfunction "O_6") (pintype "output"))
      (node (ref "E9") (pin "11") (pinfunction "CLK_11") (pintype "input"))
      (node (ref "E9") (pin "3") (pinfunction "CLK_3") (pintype "input"))
    )
    (net (code "182") (name "SCR_ACTIVE") (class "Default")
      (node (ref "J1") (pin "F") (pinfunction "P_F") (pintype "passive"))
      (node (ref "R46") (pin "2") (pinfunction "2_2") (pintype "passive"))
    )
    (net (code "183") (name "TP3") (class "Default")
      (node (ref "E24") (pin "12") (pinfunction "I1_12") (pintype "input"))
      (node (ref "OMNIBUS") (pin "CH2") (pinfunction "1_CH2") (pintype "bidirectional"))
    )
    (net (code "184") (name "VCC") (class "Default")
      (node (ref "C1") (pin "1") (pinfunction "1_1") (pintype "passive"))
      (node (ref "C10") (pin "1") (pinfunction "1_1") (pintype "passive"))
      (node (ref "C11") (pin "1") (pinfunction "1_1") (pintype "passive"))
      (node (ref "C12") (pin "1") (pinfunction "1_1") (pintype "passive"))
      (node (ref "C13") (pin "1") (pinfunction "1_1") (pintype "passive"))
      (node (ref "C14") (pin "1") (pinfunction "1_1") (pintype "passive"))
      (node (ref "C15") (pin "1") (pinfunction "1_1") (pintype "passive"))
      (node (ref "C16") (pin "1") (pinfunction "1_1") (pintype "passive"))
      (node (ref "C17") (pin "1") (pinfunction "1_1") (pintype "passive"))
      (node (ref "C18") (pin "1") (pinfunction "1_1") (pintype "passive"))
      (node (ref "C19") (pin "1") (pinfunction "1_1") (pintype "passive"))
      (node (ref "C2") (pin "1") (pinfunction "1_1") (pintype "passive"))
      (node (ref "C20") (pin "1") (pinfunction "1_1") (pintype "passive"))
      (node (ref "C21") (pin "1") (pinfunction "1_1") (pintype "passive"))
      (node (ref "C23") (pin "1") (pinfunction "1_1") (pintype "passive"))
      (node (ref "C24") (pin "1") (pinfunction "1_1") (pintype "passive"))
      (node (ref "C25") (pin "1") (pinfunction "1_1") (pintype "passive"))
      (node (ref "C26") (pin "1") (pinfunction "1_1") (pintype "passive"))
      (node (ref "C27") (pin "1") (pinfunction "1_1") (pintype "passive"))
      (node (ref "C28") (pin "1") (pinfunction "1_1") (pintype "passive"))
      (node (ref "C29") (pin "1") (pinfunction "1_1") (pintype "passive"))
      (node (ref "C3") (pin "1") (pinfunction "1_1") (pintype "passive"))
      (node (ref "C30") (pin "1") (pinfunction "1_1") (pintype "passive"))
      (node (ref "C33") (pin "1") (pinfunction "1_1") (pintype "passive"))
      (node (ref "C34") (pin "1") (pinfunction "1_1") (pintype "passive"))
      (node (ref "C35") (pin "1") (pinfunction "1_1") (pintype "passive"))
      (node (ref "C36") (pin "1") (pinfunction "1_1") (pintype "passive"))
      (node (ref "C37") (pin "1") (pinfunction "1_1") (pintype "passive"))
      (node (ref "C38") (pin "1") (pinfunction "1_1") (pintype "passive"))
      (node (ref "C39") (pin "1") (pinfunction "1_1") (pintype "passive"))
      (node (ref "C4") (pin "1") (pinfunction "1_1") (pintype "passive"))
      (node (ref "C40") (pin "1") (pinfunction "1_1") (pintype "passive"))
      (node (ref "C41") (pin "1") (pinfunction "1_1") (pintype "passive"))
      (node (ref "C42") (pin "1") (pinfunction "1_1") (pintype "passive"))
      (node (ref "C43") (pin "1") (pinfunction "1_1") (pintype "passive"))
      (node (ref "C44") (pin "1") (pinfunction "1_1") (pintype "passive"))
      (node (ref "C45") (pin "+") (pinfunction "+_+") (pintype "passive"))
      (node (ref "C46") (pin "+") (pinfunction "+_+") (pintype "passive"))
      (node (ref "C47") (pin "+") (pinfunction "+_+") (pintype "passive"))
      (node (ref "C5") (pin "1") (pinfunction "1_1") (pintype "passive"))
      (node (ref "C50") (pin "1") (pinfunction "1_1") (pintype "passive"))
      (node (ref "C6") (pin "1") (pinfunction "1_1") (pintype "passive"))
      (node (ref "C7") (pin "1") (pinfunction "1_1") (pintype "passive"))
      (node (ref "C8") (pin "1") (pinfunction "1_1") (pintype "passive"))
      (node (ref "C9") (pin "1") (pinfunction "1_1") (pintype "passive"))
      (node (ref "E21") (pin "1") (pinfunction "I0_1") (pintype "input"))
      (node (ref "E25") (pin "1") (pinfunction "I0_1") (pintype "input"))
      (node (ref "E27") (pin "6") (pinfunction "G1_6") (pintype "input"))
      (node (ref "E31") (pin "6") (pinfunction "G1_6") (pintype "input"))
      (node (ref "OMNIBUS") (pin "AA2") (pinfunction "1_AA2") (pintype "bidirectional"))
      (node (ref "OMNIBUS") (pin "BA2") (pinfunction "1_BA2") (pintype "bidirectional"))
      (node (ref "OMNIBUS") (pin "CA2") (pinfunction "1_CA2") (pintype "bidirectional"))
      (node (ref "R10") (pin "2") (pinfunction "2_2") (pintype "passive"))
      (node (ref "R14") (pin "2") (pinfunction "2_2") (pintype "passive"))
      (node (ref "R15") (pin "2") (pinfunction "2_2") (pintype "passive"))
      (node (ref "R16") (pin "2") (pinfunction "2_2") (pintype "passive"))
      (node (ref "R17") (pin "2") (pinfunction "2_2") (pintype "passive"))
      (node (ref "R19") (pin "2") (pinfunction "2_2") (pintype "passive"))
      (node (ref "R28") (pin "2") (pinfunction "2_2") (pintype "passive"))
      (node (ref "R3") (pin "2") (pinfunction "2_2") (pintype "passive"))
      (node (ref "R30") (pin "2") (pinfunction "2_2") (pintype "passive"))
      (node (ref "R33") (pin "2") (pinfunction "2_2") (pintype "passive"))
      (node (ref "R37") (pin "1") (pinfunction "1_1") (pintype "passive"))
      (node (ref "R4") (pin "2") (pinfunction "2_2") (pintype "passive"))
      (node (ref "R40") (pin "2") (pinfunction "2_2") (pintype "passive"))
      (node (ref "R41") (pin "2") (pinfunction "2_2") (pintype "passive"))
      (node (ref "R42") (pin "2") (pinfunction "2_2") (pintype "passive"))
      (node (ref "R43") (pin "2") (pinfunction "2_2") (pintype "passive"))
      (node (ref "R47") (pin "2") (pinfunction "2_2") (pintype "passive"))
      (node (ref "R48") (pin "2") (pinfunction "2_2") (pintype "passive"))
      (node (ref "R49") (pin "2") (pinfunction "2_2") (pintype "passive"))
      (node (ref "R52") (pin "2") (pinfunction "2_2") (pintype "passive"))
      (node (ref "R7") (pin "2") (pinfunction "2_2") (pintype "passive"))
      (node (ref "R8") (pin "2") (pinfunction "2_2") (pintype "passive"))
      (node (ref "R9") (pin "2") (pinfunction "2_2") (pintype "passive"))
    )
    (net (code "185") (name "unconnected-(E2B-Q-Pad9)") (class "Default")
      (node (ref "E2") (pin "9") (pinfunction "Q_9") (pintype "output"))
    )
    (net (code "186") (name "unconnected-(E4A-Q-Pad6)") (class "Default")
      (node (ref "E4") (pin "6") (pinfunction "Q_6") (pintype "output"))
    )
    (net (code "187") (name "unconnected-(E4A-R-Pad9)") (class "Default")
      (node (ref "E4") (pin "9") (pinfunction "R_9") (pintype "input"))
    )
    (net (code "188") (name "unconnected-(E7A-R-Pad9)") (class "Default")
      (node (ref "E7") (pin "9") (pinfunction "R_9") (pintype "input"))
    )
    (net (code "189") (name "unconnected-(E10A-Q-Pad5)") (class "Default")
      (node (ref "E10") (pin "5") (pinfunction "Q_5") (pintype "output"))
    )
    (net (code "190") (name "unconnected-(E10B-~{Q}-Pad8)") (class "Default")
      (node (ref "E10") (pin "8") (pinfunction "~{Q}_8") (pintype "output"))
    )
    (net (code "191") (name "unconnected-(E12A-Q-Pad5)") (class "Default")
      (node (ref "E12") (pin "5") (pinfunction "Q_5") (pintype "output"))
    )
    (net (code "192") (name "unconnected-(E12B-~{Q}-Pad8)") (class "Default")
      (node (ref "E12") (pin "8") (pinfunction "~{Q}_8") (pintype "output"))
    )
    (net (code "193") (name "unconnected-(E14A-~{Q}-Pad6)") (class "Default")
      (node (ref "E14") (pin "6") (pinfunction "~{Q}_6") (pintype "output"))
    )
    (net (code "194") (name "unconnected-(E14B-Q-Pad9)") (class "Default")
      (node (ref "E14") (pin "9") (pinfunction "Q_9") (pintype "output"))
    )
    (net (code "195") (name "unconnected-(E15A-Q-Pad6)") (class "Default")
      (node (ref "E15") (pin "6") (pinfunction "Q_6") (pintype "output"))
    )
    (net (code "196") (name "unconnected-(E15A-R-Pad9)") (class "Default")
      (node (ref "E15") (pin "9") (pinfunction "R_9") (pintype "input"))
    )
    (net (code "197") (name "unconnected-(E19A-R-Pad9)") (class "Default")
      (node (ref "E19") (pin "9") (pinfunction "R_9") (pintype "input"))
    )
    (net (code "198") (name "unconnected-(E19A-~{Q}-Pad1)") (class "Default")
      (node (ref "E19") (pin "1") (pinfunction "~{Q}_1") (pintype "output"))
    )
    (net (code "199") (name "unconnected-(E20F-O-Pad12)") (class "Default")
      (node (ref "E20") (pin "12") (pinfunction "O_12") (pintype "output"))
    )
    (net (code "200") (name "unconnected-(E23B-O-Pad6)") (class "Default")
      (node (ref "E23") (pin "6") (pinfunction "O_6") (pintype "output"))
    )
    (net (code "201") (name "unconnected-(E24C-O-Pad10)") (class "Default")
      (node (ref "E24") (pin "10") (pinfunction "O_10") (pintype "output"))
    )
    (net (code "202") (name "unconnected-(E27A-Y0-Pad15)") (class "Default")
      (node (ref "E27") (pin "15") (pinfunction "Y0_15") (pintype "output"))
    )
    (net (code "203") (name "unconnected-(E27A-Y2-Pad13)") (class "Default")
      (node (ref "E27") (pin "13") (pinfunction "Y2_13") (pintype "output"))
    )
    (net (code "204") (name "unconnected-(E27A-Y4-Pad11)") (class "Default")
      (node (ref "E27") (pin "11") (pinfunction "Y4_11") (pintype "output"))
    )
    (net (code "205") (name "unconnected-(E31A-Y0-Pad15)") (class "Default")
      (node (ref "E31") (pin "15") (pinfunction "Y0_15") (pintype "output"))
    )
    (net (code "206") (name "unconnected-(E31A-Y2-Pad13)") (class "Default")
      (node (ref "E31") (pin "13") (pinfunction "Y2_13") (pintype "output"))
    )
    (net (code "207") (name "unconnected-(E31A-Y4-Pad11)") (class "Default")
      (node (ref "E31") (pin "11") (pinfunction "Y4_11") (pintype "output"))
    )
    (net (code "208") (name "unconnected-(IC34A-~{Q1}-Pad3)") (class "Default")
      (node (ref "IC34") (pin "3") (pinfunction "~{Q1}_3") (pintype "output"))
    )
    (net (code "209") (name "unconnected-(IC34A-~{Q2}-Pad6)") (class "Default")
      (node (ref "IC34") (pin "6") (pinfunction "~{Q2}_6") (pintype "output"))
    )
    (net (code "210") (name "unconnected-(IC34A-~{Q3}-Pad11)") (class "Default")
      (node (ref "IC34") (pin "11") (pinfunction "~{Q3}_11") (pintype "output"))
    )
    (net (code "211") (name "unconnected-(IC34A-~{Q4}-Pad14)") (class "Default")
      (node (ref "IC34") (pin "14") (pinfunction "~{Q4}_14") (pintype "output"))
    )
    (net (code "212") (name "unconnected-(IC37A-~{Q1}-Pad3)") (class "Default")
      (node (ref "IC37") (pin "3") (pinfunction "~{Q1}_3") (pintype "output"))
    )
    (net (code "213") (name "unconnected-(IC37A-~{Q2}-Pad6)") (class "Default")
      (node (ref "IC37") (pin "6") (pinfunction "~{Q2}_6") (pintype "output"))
    )
    (net (code "214") (name "unconnected-(IC37A-~{Q3}-Pad11)") (class "Default")
      (node (ref "IC37") (pin "11") (pinfunction "~{Q3}_11") (pintype "output"))
    )
    (net (code "215") (name "unconnected-(IC37A-~{Q4}-Pad14)") (class "Default")
      (node (ref "IC37") (pin "14") (pinfunction "~{Q4}_14") (pintype "output"))
    )
    (net (code "216") (name "unconnected-(IC40A-~{Q1}-Pad3)") (class "Default")
      (node (ref "IC40") (pin "3") (pinfunction "~{Q1}_3") (pintype "output"))
    )
    (net (code "217") (name "unconnected-(IC40A-~{Q2}-Pad6)") (class "Default")
      (node (ref "IC40") (pin "6") (pinfunction "~{Q2}_6") (pintype "output"))
    )
    (net (code "218") (name "unconnected-(IC40A-~{Q3}-Pad11)") (class "Default")
      (node (ref "IC40") (pin "11") (pinfunction "~{Q3}_11") (pintype "output"))
    )
    (net (code "219") (name "unconnected-(IC40A-~{Q4}-Pad14)") (class "Default")
      (node (ref "IC40") (pin "14") (pinfunction "~{Q4}_14") (pintype "output"))
    )
    (net (code "220") (name "unconnected-(IC43A-~{Q1}-Pad3)") (class "Default")
      (node (ref "IC43") (pin "3") (pinfunction "~{Q1}_3") (pintype "output"))
    )
    (net (code "221") (name "unconnected-(IC43A-~{Q2}-Pad6)") (class "Default")
      (node (ref "IC43") (pin "6") (pinfunction "~{Q2}_6") (pintype "output"))
    )
    (net (code "222") (name "unconnected-(IC43A-~{Q3}-Pad11)") (class "Default")
      (node (ref "IC43") (pin "11") (pinfunction "~{Q3}_11") (pintype "output"))
    )
    (net (code "223") (name "unconnected-(IC43A-~{Q4}-Pad14)") (class "Default")
      (node (ref "IC43") (pin "14") (pinfunction "~{Q4}_14") (pintype "output"))
    )
    (net (code "224") (name "~{AB}") (class "Default")
      (node (ref "E11") (pin "1") (pinfunction "I0_1") (pintype "input"))
      (node (ref "E32") (pin "5") (pinfunction "I1_5") (pintype "input"))
      (node (ref "E6") (pin "8") (pinfunction "O_8") (pintype "output"))
    )
    (net (code "225") (name "~{BA}") (class "Default")
      (node (ref "E3") (pin "4") (pinfunction "O_4") (pintype "output"))
      (node (ref "J2") (pin "FF") (pinfunction "P_FF") (pintype "passive"))
    )
    (net (code "226") (name "~{BB}") (class "Default")
      (node (ref "E3") (pin "2") (pinfunction "O_2") (pintype "output"))
      (node (ref "J2") (pin "LL") (pinfunction "P_LL") (pintype "passive"))
    )
    (net (code "227") (name "~{C1}") (class "Default")
      (node (ref "E17") (pin "8") (pinfunction "O_8") (pintype "open_collector"))
      (node (ref "OMNIBUS") (pin "CH1") (pinfunction "1_CH1") (pintype "bidirectional"))
    )
    (net (code "228") (name "~{CATCH_PULSE}") (class "Default")
      (node (ref "E6") (pin "11") (pinfunction "O_11") (pintype "output"))
      (node (ref "E6") (pin "4") (pinfunction "I0_4") (pintype "input"))
    )
    (net (code "229") (name "~{CLOCK_PULSE}") (class "Default")
      (node (ref "E11") (pin "3") (pinfunction "I0_3") (pintype "input"))
      (node (ref "E5") (pin "3") (pinfunction "O_3") (pintype "output"))
      (node (ref "E8") (pin "11") (pinfunction "I_11") (pintype "input"))
    )
    (net (code "230") (name "~{DATA04}") (class "Default")
      (node (ref "E33") (pin "3") (pinfunction "O_3") (pintype "open_collector"))
      (node (ref "E36") (pin "12") (pinfunction "I1_12") (pintype "input"))
      (node (ref "OMNIBUS") (pin "BR1") (pinfunction "1_BR1") (pintype "bidirectional"))
    )
    (net (code "231") (name "~{DATA05}") (class "Default")
      (node (ref "E33") (pin "6") (pinfunction "O_6") (pintype "open_collector"))
      (node (ref "E36") (pin "8") (pinfunction "I0_8") (pintype "input"))
      (node (ref "OMNIBUS") (pin "BS1") (pinfunction "1_BS1") (pintype "bidirectional"))
    )
    (net (code "232") (name "~{DATA06}") (class "Default")
      (node (ref "E33") (pin "11") (pinfunction "O_11") (pintype "open_collector"))
      (node (ref "E36") (pin "6") (pinfunction "I1_6") (pintype "input"))
      (node (ref "OMNIBUS") (pin "BU1") (pinfunction "1_BU1") (pintype "bidirectional"))
    )
    (net (code "233") (name "~{DATA07}") (class "Default")
      (node (ref "E33") (pin "8") (pinfunction "O_8") (pintype "open_collector"))
      (node (ref "E36") (pin "2") (pinfunction "I0_2") (pintype "input"))
      (node (ref "OMNIBUS") (pin "BV1") (pinfunction "1_BV1") (pintype "bidirectional"))
    )
    (net (code "234") (name "~{DATA08}") (class "Default")
      (node (ref "E39") (pin "3") (pinfunction "O_3") (pintype "open_collector"))
      (node (ref "E42") (pin "12") (pinfunction "I1_12") (pintype "input"))
      (node (ref "OMNIBUS") (pin "DR1") (pinfunction "1_DR1") (pintype "bidirectional"))
    )
    (net (code "235") (name "~{DATA09}") (class "Default")
      (node (ref "E39") (pin "6") (pinfunction "O_6") (pintype "open_collector"))
      (node (ref "E42") (pin "8") (pinfunction "I0_8") (pintype "input"))
      (node (ref "OMNIBUS") (pin "DS1") (pinfunction "1_DS1") (pintype "bidirectional"))
    )
    (net (code "236") (name "~{DATA10}") (class "Default")
      (node (ref "E39") (pin "8") (pinfunction "O_8") (pintype "open_collector"))
      (node (ref "E42") (pin "6") (pinfunction "I1_6") (pintype "input"))
      (node (ref "OMNIBUS") (pin "DU1") (pinfunction "1_DU1") (pintype "bidirectional"))
    )
    (net (code "237") (name "~{DATA11}") (class "Default")
      (node (ref "E39") (pin "11") (pinfunction "O_11") (pintype "open_collector"))
      (node (ref "E42") (pin "2") (pinfunction "I0_2") (pintype "input"))
      (node (ref "OMNIBUS") (pin "DV1") (pinfunction "1_DV1") (pintype "bidirectional"))
    )
    (net (code "238") (name "~{ENABLE}") (class "Default")
      (node (ref "E26") (pin "4") (pinfunction "O_4") (pintype "output"))
      (node (ref "R23") (pin "1") (pinfunction "1_1") (pintype "passive"))
    )
    (net (code "239") (name "~{ENA_PUN_BUFFR}") (class "Default")
      (node (ref "E24") (pin "4") (pinfunction "O_4") (pintype "output"))
      (node (ref "E36") (pin "11") (pinfunction "I0_11") (pintype "input"))
      (node (ref "E36") (pin "3") (pinfunction "I1_3") (pintype "input"))
      (node (ref "E36") (pin "5") (pinfunction "I0_5") (pintype "input"))
      (node (ref "E36") (pin "9") (pinfunction "I1_9") (pintype "input"))
      (node (ref "E42") (pin "11") (pinfunction "I0_11") (pintype "input"))
      (node (ref "E42") (pin "3") (pinfunction "I1_3") (pintype "input"))
      (node (ref "E42") (pin "5") (pinfunction "I0_5") (pintype "input"))
      (node (ref "E42") (pin "9") (pinfunction "I1_9") (pintype "input"))
    )
    (net (code "240") (name "~{INIT+EOT}") (class "Default")
      (node (ref "E1") (pin "13") (pinfunction "I2_13") (pintype "input"))
      (node (ref "E2") (pin "1") (pinfunction "CLR_1") (pintype "input"))
      (node (ref "E8") (pin "6") (pinfunction "O_6") (pintype "output"))
    )
    (net (code "241") (name "~{INITIALIZE}") (class "Default")
      (node (ref "E10") (pin "1") (pinfunction "CLR_1") (pintype "input"))
      (node (ref "E14") (pin "4") (pinfunction "PRE_4") (pintype "input"))
      (node (ref "E2") (pin "13") (pinfunction "CLR_13") (pintype "input"))
      (node (ref "E30") (pin "4") (pinfunction "O_4") (pintype "output"))
      (node (ref "E35") (pin "10") (pinfunction "I1_10") (pintype "input"))
      (node (ref "E35") (pin "9") (pinfunction "I0_9") (pintype "input"))
      (node (ref "E5") (pin "5") (pinfunction "I1_5") (pintype "input"))
    )
    (net (code "242") (name "~{INTERNAL_IO}") (class "Default")
      (node (ref "E17") (pin "3") (pinfunction "O_3") (pintype "open_collector"))
      (node (ref "E17") (pin "6") (pinfunction "O_6") (pintype "open_collector"))
      (node (ref "OMNIBUS") (pin "CL1") (pinfunction "1_CL1") (pintype "bidirectional"))
    )
    (net (code "243") (name "~{INTERRUPT}") (class "Default")
      (node (ref "E18") (pin "11") (pinfunction "O_11") (pintype "open_collector"))
      (node (ref "E18") (pin "8") (pinfunction "O_8") (pintype "open_collector"))
      (node (ref "OMNIBUS") (pin "CP1") (pinfunction "1_CP1") (pintype "bidirectional"))
    )
    (net (code "244") (name "~{MD3}") (class "Default")
      (node (ref "E21") (pin "2") (pinfunction "I1_2") (pintype "input"))
      (node (ref "E25") (pin "2") (pinfunction "I1_2") (pintype "input"))
      (node (ref "OMNIBUS") (pin "AP1") (pinfunction "1_AP1") (pintype "bidirectional"))
    )
    (net (code "245") (name "~{MD4}") (class "Default")
      (node (ref "E21") (pin "3") (pinfunction "I2_3") (pintype "input"))
      (node (ref "E25") (pin "3") (pinfunction "I2_3") (pintype "input"))
      (node (ref "OMNIBUS") (pin "BK1") (pinfunction "1_BK1") (pintype "bidirectional"))
    )
    (net (code "246") (name "~{MD5}") (class "Default")
      (node (ref "E21") (pin "4") (pinfunction "I3_4") (pintype "input"))
      (node (ref "E25") (pin "4") (pinfunction "I3_4") (pintype "input"))
      (node (ref "OMNIBUS") (pin "BL1") (pinfunction "1_BL1") (pintype "bidirectional"))
    )
    (net (code "247") (name "~{MD6}") (class "Default")
      (node (ref "E21") (pin "5") (pinfunction "I4_5") (pintype "input"))
      (node (ref "E25") (pin "5") (pinfunction "I4_5") (pintype "input"))
      (node (ref "OMNIBUS") (pin "BM1") (pinfunction "1_BM1") (pintype "bidirectional"))
    )
    (net (code "248") (name "~{MD7}") (class "Default")
      (node (ref "E20") (pin "5") (pinfunction "I_5") (pintype "input"))
      (node (ref "E21") (pin "6") (pinfunction "I5_6") (pintype "input"))
      (node (ref "OMNIBUS") (pin "BP1") (pinfunction "1_BP1") (pintype "bidirectional"))
    )
    (net (code "249") (name "~{MD8}") (class "Default")
      (node (ref "E20") (pin "1") (pinfunction "I_1") (pintype "input"))
      (node (ref "E25") (pin "11") (pinfunction "I6_11") (pintype "input"))
      (node (ref "OMNIBUS") (pin "DK1") (pinfunction "1_DK1") (pintype "bidirectional"))
    )
    (net (code "250") (name "~{MD9}") (class "Default")
      (node (ref "E30") (pin "12") (pinfunction "I1_12") (pintype "input"))
      (node (ref "OMNIBUS") (pin "DL1") (pinfunction "1_DL1") (pintype "bidirectional"))
    )
    (net (code "251") (name "~{MD10}") (class "Default")
      (node (ref "E30") (pin "8") (pinfunction "I0_8") (pintype "input"))
      (node (ref "OMNIBUS") (pin "DM1") (pinfunction "1_DM1") (pintype "bidirectional"))
    )
    (net (code "252") (name "~{MD11}") (class "Default")
      (node (ref "E30") (pin "2") (pinfunction "I0_2") (pintype "input"))
      (node (ref "OMNIBUS") (pin "DP1") (pinfunction "1_DP1") (pintype "bidirectional"))
    )
    (net (code "253") (name "~{MOTOR_STOPPING}") (class "Default")
      (node (ref "E11") (pin "5") (pinfunction "I2_5") (pintype "input"))
      (node (ref "E12") (pin "3") (pinfunction "CLK_3") (pintype "input"))
      (node (ref "E4") (pin "1") (pinfunction "~{Q}_1") (pintype "output"))
      (node (ref "OMNIBUS") (pin "BA1") (pinfunction "1_BA1") (pintype "bidirectional"))
    )
    (net (code "254") (name "~{MULTI_OUT}") (class "Default")
      (node (ref "D6") (pin "C") (pinfunction "C_C") (pintype "passive"))
      (node (ref "E3") (pin "11") (pinfunction "I_11") (pintype "input"))
      (node (ref "Q6") (pin "1") (pinfunction "E_1") (pintype "passive"))
      (node (ref "R34") (pin "1") (pinfunction "1_1") (pintype "passive"))
      (node (ref "R35") (pin "1") (pinfunction "1_1") (pintype "passive"))
      (node (ref "R44") (pin "2") (pinfunction "2_2") (pintype "passive"))
    )
    (net (code "255") (name "~{PAUSE}") (class "Default")
      (node (ref "E20") (pin "11") (pinfunction "I_11") (pintype "input"))
      (node (ref "OMNIBUS") (pin "CD1") (pinfunction "1_CD1") (pintype "bidirectional"))
    )
    (net (code "256") (name "~{PCE}") (class "Default")
      (node (ref "E27") (pin "7") (pinfunction "Y7_7") (pintype "output"))
      (node (ref "E29") (pin "9") (pinfunction "I_9") (pintype "input"))
    )
    (net (code "257") (name "~{PCF}") (class "Default")
      (node (ref "E27") (pin "10") (pinfunction "Y5_10") (pintype "output"))
      (node (ref "E28") (pin "9") (pinfunction "I0_9") (pintype "input"))
    )
    (net (code "258") (name "~{PPC}") (class "Default")
      (node (ref "E27") (pin "12") (pinfunction "Y3_12") (pintype "output"))
      (node (ref "E28") (pin "13") (pinfunction "I1_13") (pintype "input"))
    )
    (net (code "259") (name "~{PSF}") (class "Default")
      (node (ref "E27") (pin "9") (pinfunction "Y6_9") (pintype "output"))
      (node (ref "E29") (pin "11") (pinfunction "I_11") (pintype "input"))
    )
    (net (code "260") (name "~{PUNCH_DONE}") (class "Default")
      (node (ref "E10") (pin "3") (pinfunction "CLK_3") (pintype "input"))
      (node (ref "E14") (pin "10") (pinfunction "PRE_10") (pintype "input"))
      (node (ref "E15") (pin "1") (pinfunction "~{Q}_1") (pintype "output"))
      (node (ref "E26") (pin "13") (pinfunction "I_13") (pintype "input"))
    )
    (net (code "261") (name "~{PUNCH_FEED}") (class "Default")
      (node (ref "C64") (pin "1") (pinfunction "1_1") (pintype "passive"))
      (node (ref "E13") (pin "1") (pinfunction "I0_1") (pintype "input"))
      (node (ref "IC37") (pin "1") (pinfunction "CLR_1") (pintype "input"))
      (node (ref "IC43") (pin "1") (pinfunction "CLR_1") (pintype "input"))
      (node (ref "J1") (pin "D") (pinfunction "P_D") (pintype "passive"))
      (node (ref "R7") (pin "1") (pinfunction "1_1") (pintype "passive"))
    )
    (net (code "262") (name "~{PUNCH_STROBE}") (class "Default")
      (node (ref "E10") (pin "4") (pinfunction "PRE_4") (pintype "input"))
      (node (ref "E22") (pin "11") (pinfunction "O_11") (pintype "output"))
      (node (ref "E26") (pin "5") (pinfunction "I_5") (pintype "input"))
    )
    (net (code "263") (name "~{RBC}") (class "Default")
      (node (ref "E28") (pin "1") (pinfunction "I0_1") (pintype "input"))
      (node (ref "E28") (pin "4") (pinfunction "I0_4") (pintype "input"))
      (node (ref "E31") (pin "14") (pinfunction "Y1_14") (pintype "output"))
    )
    (net (code "264") (name "~{RDR_RUN}") (class "Default")
      (node (ref "E11") (pin "13") (pinfunction "I2_13") (pintype "input"))
      (node (ref "E2") (pin "6") (pinfunction "~{Q}_6") (pintype "output"))
    )
    (net (code "265") (name "~{RFC}") (class "Default")
      (node (ref "E28") (pin "5") (pinfunction "I1_5") (pintype "input"))
      (node (ref "E31") (pin "12") (pinfunction "Y3_12") (pintype "output"))
    )
    (net (code "266") (name "~{RIOP2}") (class "Default")
      (node (ref "E1") (pin "1") (pinfunction "I0_1") (pintype "input"))
      (node (ref "E22") (pin "3") (pinfunction "O_3") (pintype "output"))
    )
    (net (code "267") (name "~{RIOP4}") (class "Default")
      (node (ref "E1") (pin "2") (pinfunction "I1_2") (pintype "input"))
      (node (ref "E11") (pin "8") (pinfunction "O_8") (pintype "output"))
      (node (ref "E2") (pin "4") (pinfunction "PRE_4") (pintype "input"))
    )
    (net (code "268") (name "~{RPE}") (class "Default")
      (node (ref "E29") (pin "3") (pinfunction "I_3") (pintype "input"))
      (node (ref "E31") (pin "7") (pinfunction "Y7_7") (pintype "output"))
    )
    (net (code "269") (name "~{RRB}") (class "Default")
      (node (ref "E28") (pin "2") (pinfunction "I1_2") (pintype "input"))
      (node (ref "E31") (pin "10") (pinfunction "Y5_10") (pintype "output"))
    )
    (net (code "270") (name "~{RSF}") (class "Default")
      (node (ref "E29") (pin "1") (pinfunction "I_1") (pintype "input"))
      (node (ref "E31") (pin "9") (pinfunction "Y6_9") (pintype "output"))
    )
    (net (code "271") (name "~{R_FEED_SW}") (class "Default")
      (node (ref "C63") (pin "1") (pinfunction "1_1") (pintype "passive"))
      (node (ref "E5") (pin "13") (pinfunction "I1_13") (pintype "input"))
      (node (ref "E6") (pin "1") (pinfunction "I0_1") (pintype "input"))
      (node (ref "J2") (pin "TT") (pinfunction "P_TT") (pintype "passive"))
      (node (ref "R49") (pin "1") (pinfunction "1_1") (pintype "passive"))
    )
    (net (code "272") (name "~{R_OFFLINE}") (class "Default")
      (node (ref "C51") (pin "1") (pinfunction "1_1") (pintype "passive"))
      (node (ref "E23") (pin "10") (pinfunction "I1_10") (pintype "input"))
      (node (ref "J2") (pin "F") (pinfunction "P_F") (pintype "passive"))
      (node (ref "R6") (pin "2") (pinfunction "2_2") (pintype "passive"))
    )
    (net (code "273") (name "~{SHIFT_PULSE}") (class "Default")
      (node (ref "E1") (pin "6") (pinfunction "O_6") (pintype "output"))
      (node (ref "E12") (pin "4") (pinfunction "PRE_4") (pintype "input"))
      (node (ref "E6") (pin "5") (pinfunction "I1_5") (pintype "input"))
    )
    (net (code "274") (name "~{SKIP}") (class "Default")
      (node (ref "E18") (pin "3") (pinfunction "O_3") (pintype "open_collector"))
      (node (ref "E18") (pin "6") (pinfunction "O_6") (pintype "open_collector"))
      (node (ref "OMNIBUS") (pin "CS1") (pinfunction "1_CS1") (pintype "bidirectional"))
    )
  )
)
